# micr0x.net
KiCad netlist of a schematic drawn in EAGLE
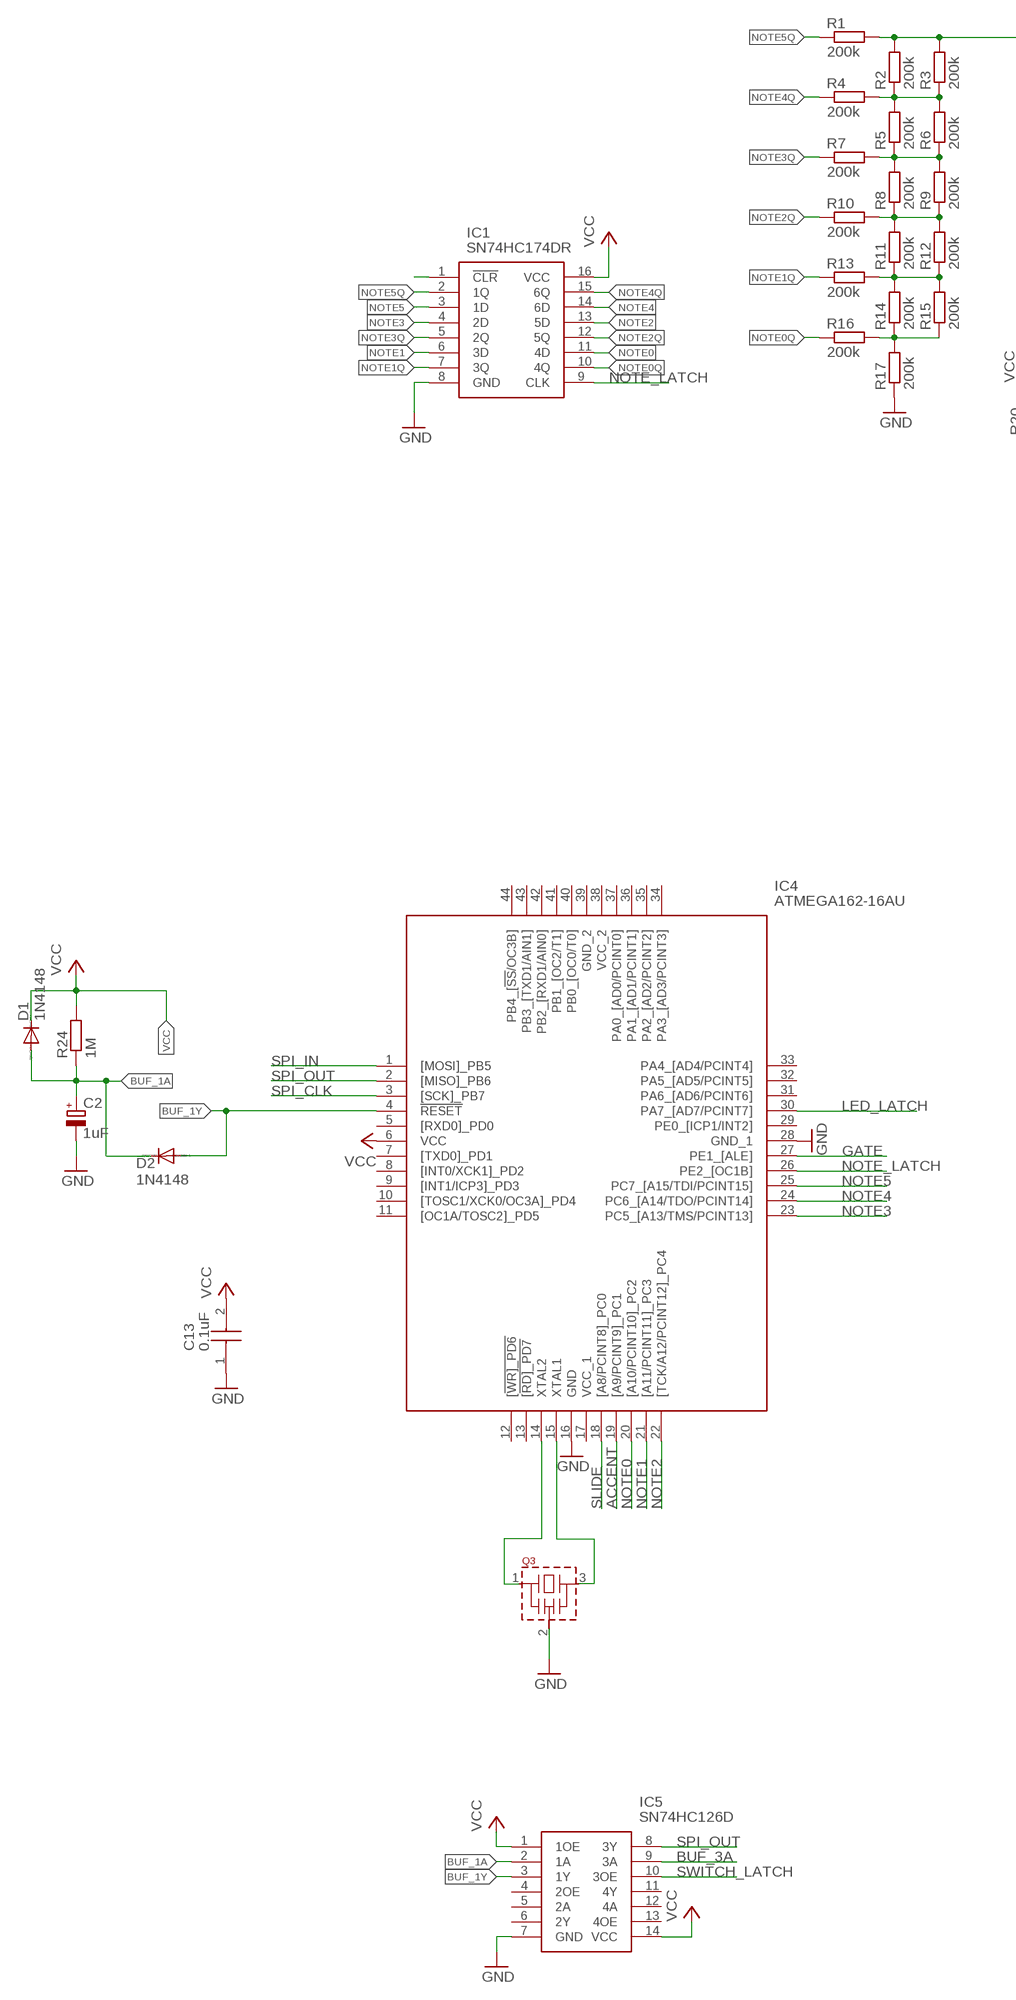
[diagram p0: schematic, sheet 1, part 1 of 2]
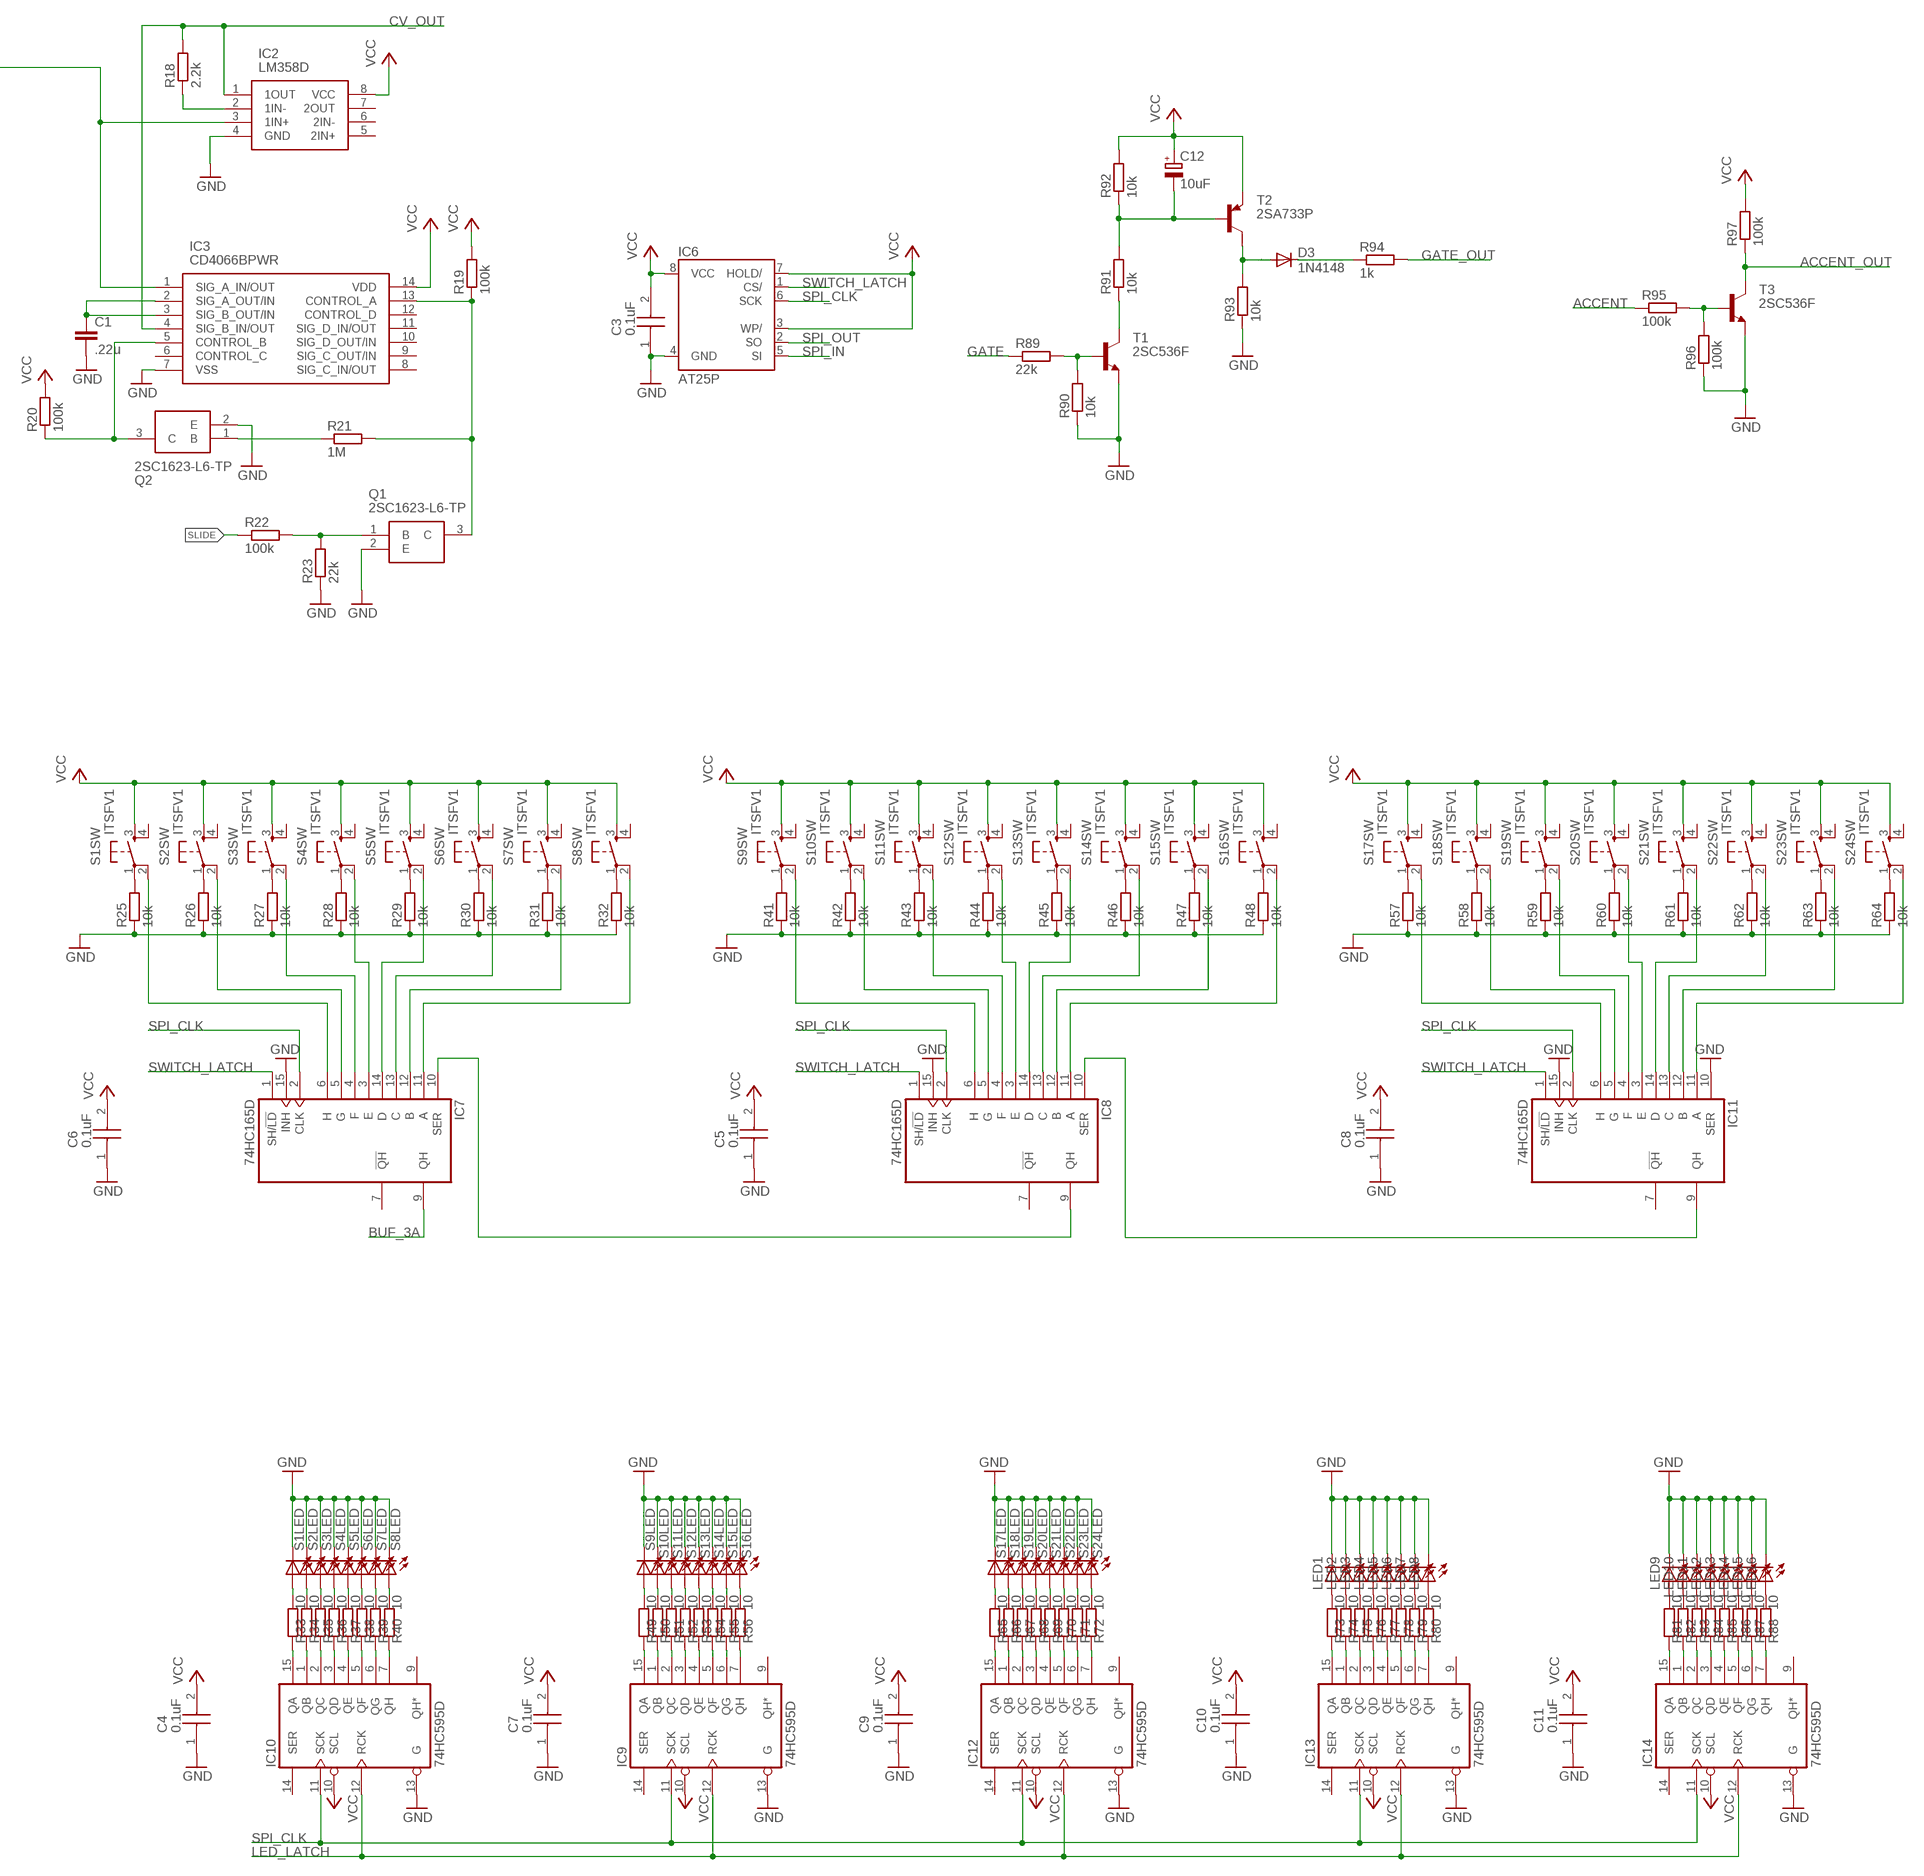
[diagram p1: schematic, sheet 1, part 2 of 2]

(export (version "E")
  (design (tool "Eeschema 10.0.6"))
  (components
    (comp (ref "C1")
      (value ".22u")
      (footprint "eagle-import:C075-032X103")
      (fields (field (name "MOUSER_PART_NUMBER") "QYX2A224KTP"))
      (libsource (lib "eagle-import") (part "C-EU075-032X103"))
    )
    (comp (ref "C2")
      (value "1uF")
      (footprint "eagle-import:E2-5")
      (fields (field (name "MOUSER_PART_NUMBER") "140-REA1R0M2CBK0511P"))
      (libsource (lib "eagle-import") (part "CPOL-EUE2-5"))
    )
    (comp (ref "C3")
      (value "0.1uF")
      (footprint "eagle-import:CAPC1608X90N")
      (fields
        (field (name "MANUFACTURER_PART_NUMBER") "GCJ188R71H104KA12D")
        (field (name "MOUSER_PART_NUMBER") "81-GCJ188R71H104KA2D")
      )
      (libsource (lib "eagle-import") (part "GCJ188R71H104KA12D"))
    )
    (comp (ref "C4")
      (value "0.1uF")
      (footprint "eagle-import:CAPC1608X90N")
      (fields
        (field (name "MANUFACTURER_PART_NUMBER") "GCJ188R71H104KA12D")
        (field (name "MOUSER_PART_NUMBER") "81-GCJ188R71H104KA2D")
      )
      (libsource (lib "eagle-import") (part "GCJ188R71H104KA12D"))
    )
    (comp (ref "C5")
      (value "0.1uF")
      (footprint "eagle-import:CAPC1608X90N")
      (fields
        (field (name "MANUFACTURER_PART_NUMBER") "GCJ188R71H104KA12D")
        (field (name "MOUSER_PART_NUMBER") "81-GCJ188R71H104KA2D")
      )
      (libsource (lib "eagle-import") (part "GCJ188R71H104KA12D"))
    )
    (comp (ref "C6")
      (value "0.1uF")
      (footprint "eagle-import:CAPC1608X90N")
      (fields
        (field (name "MANUFACTURER_PART_NUMBER") "GCJ188R71H104KA12D")
        (field (name "MOUSER_PART_NUMBER") "81-GCJ188R71H104KA2D")
      )
      (libsource (lib "eagle-import") (part "GCJ188R71H104KA12D"))
    )
    (comp (ref "C7")
      (value "0.1uF")
      (footprint "eagle-import:CAPC1608X90N")
      (fields
        (field (name "MANUFACTURER_PART_NUMBER") "GCJ188R71H104KA12D")
        (field (name "MOUSER_PART_NUMBER") "81-GCJ188R71H104KA2D")
      )
      (libsource (lib "eagle-import") (part "GCJ188R71H104KA12D"))
    )
    (comp (ref "C8")
      (value "0.1uF")
      (footprint "eagle-import:CAPC1608X90N")
      (fields
        (field (name "MANUFACTURER_PART_NUMBER") "GCJ188R71H104KA12D")
        (field (name "MOUSER_PART_NUMBER") "81-GCJ188R71H104KA2D")
      )
      (libsource (lib "eagle-import") (part "GCJ188R71H104KA12D"))
    )
    (comp (ref "C9")
      (value "0.1uF")
      (footprint "eagle-import:CAPC1608X90N")
      (fields
        (field (name "MANUFACTURER_PART_NUMBER") "GCJ188R71H104KA12D")
        (field (name "MOUSER_PART_NUMBER") "81-GCJ188R71H104KA2D")
      )
      (libsource (lib "eagle-import") (part "GCJ188R71H104KA12D"))
    )
    (comp (ref "C10")
      (value "0.1uF")
      (footprint "eagle-import:CAPC1608X90N")
      (fields
        (field (name "MANUFACTURER_PART_NUMBER") "GCJ188R71H104KA12D")
        (field (name "MOUSER_PART_NUMBER") "81-GCJ188R71H104KA2D")
      )
      (libsource (lib "eagle-import") (part "GCJ188R71H104KA12D"))
    )
    (comp (ref "C11")
      (value "0.1uF")
      (footprint "eagle-import:CAPC1608X90N")
      (fields
        (field (name "MANUFACTURER_PART_NUMBER") "GCJ188R71H104KA12D")
        (field (name "MOUSER_PART_NUMBER") "81-GCJ188R71H104KA2D")
      )
      (libsource (lib "eagle-import") (part "GCJ188R71H104KA12D"))
    )
    (comp (ref "C12")
      (value "10uF")
      (footprint "eagle-import:E2-5")
      (libsource (lib "eagle-import") (part "CPOL-EUE2-5"))
    )
    (comp (ref "C13")
      (value "0.1uF")
      (footprint "eagle-import:CAPC1608X90N")
      (fields
        (field (name "MANUFACTURER_PART_NUMBER") "GCJ188R71H104KA12D")
        (field (name "MOUSER_PART_NUMBER") "81-GCJ188R71H104KA2D")
      )
      (libsource (lib "eagle-import") (part "GCJ188R71H104KA12D"))
    )
    (comp (ref "D1")
      (value "1N4148")
      (footprint "eagle-import:DO35-7")
      (libsource (lib "eagle-import") (part "1N4148DO35-7"))
    )
    (comp (ref "D2")
      (value "1N4148")
      (footprint "eagle-import:DO35-7")
      (libsource (lib "eagle-import") (part "1N4148DO35-7"))
    )
    (comp (ref "D3")
      (value "1N4148")
      (footprint "eagle-import:DO35-7")
      (libsource (lib "eagle-import") (part "1N4148DO35-7"))
    )
    (comp (ref "IC1")
      (value "SN74HC174DR")
      (footprint "eagle-import:SOIC127P600X175-16N")
      (fields (field (name "MOUSER_PART_NUMBER") "595-SN74HC174DR"))
      (libsource (lib "eagle-import") (part "SN74HC174DR"))
    )
    (comp (ref "IC2")
      (value "LM358D")
      (footprint "eagle-import:SOIC127P600X175-8N")
      (fields (field (name "MOUSER_PART_NUMBER") "595-LM358D"))
      (libsource (lib "eagle-import") (part "LM358D"))
    )
    (comp (ref "IC3")
      (value "CD4066BPWR")
      (footprint "eagle-import:SOP65P640X120-14N")
      (libsource (lib "eagle-import") (part "CD4066BPWR"))
    )
    (comp (ref "IC4")
      (value "ATMEGA162-16AU")
      (footprint "eagle-import:QFP80P1200X1200X120-44N")
      (fields (field (name "MOUSER_PART_NUMBER") "556-ATMEGA162-16AU"))
      (libsource (lib "eagle-import") (part "ATMEGA162-16AU"))
    )
    (comp (ref "IC5")
      (value "SN74HC126D")
      (footprint "eagle-import:SOIC127P600X175-14N")
      (fields (field (name "MOUSER_PART_NUMBER") "595-SN74HC126D"))
      (libsource (lib "eagle-import") (part "SN74HC126D"))
    )
    (comp (ref "IC6")
      (value "AT25P")
      (footprint "eagle-import:DIL08")
      (fields (field (name "MPN") "CAT25040LI-G"))
      (libsource (lib "eagle-import") (part "AT25P"))
    )
    (comp (ref "IC7")
      (value "74HC165D")
      (footprint "eagle-import:SO16")
      (libsource (lib "eagle-import") (part "74165DHC"))
    )
    (comp (ref "IC8")
      (value "74HC165D")
      (footprint "eagle-import:SO16")
      (libsource (lib "eagle-import") (part "74165DHC"))
    )
    (comp (ref "IC9")
      (value "74HC595D")
      (footprint "eagle-import:SO16")
      (libsource (lib "eagle-import") (part "74595DHC"))
    )
    (comp (ref "IC10")
      (value "74HC595D")
      (footprint "eagle-import:SO16")
      (libsource (lib "eagle-import") (part "74595DHC"))
    )
    (comp (ref "IC11")
      (value "74HC165D")
      (footprint "eagle-import:SO16")
      (libsource (lib "eagle-import") (part "74165DHC"))
    )
    (comp (ref "IC12")
      (value "74HC595D")
      (footprint "eagle-import:SO16")
      (libsource (lib "eagle-import") (part "74595DHC"))
    )
    (comp (ref "IC13")
      (value "74HC595D")
      (footprint "eagle-import:SO16")
      (libsource (lib "eagle-import") (part "74595DHC"))
    )
    (comp (ref "IC14")
      (value "74HC595D")
      (footprint "eagle-import:SO16")
      (libsource (lib "eagle-import") (part "74595DHC"))
    )
    (comp (ref "LED1")
      (value "LED3MM")
      (footprint "eagle-import:LED3MM")
      (libsource (lib "eagle-import") (part "LED3MM"))
    )
    (comp (ref "LED2")
      (value "LED3MM")
      (footprint "eagle-import:LED3MM")
      (libsource (lib "eagle-import") (part "LED3MM"))
    )
    (comp (ref "LED3")
      (value "LED3MM")
      (footprint "eagle-import:LED3MM")
      (libsource (lib "eagle-import") (part "LED3MM"))
    )
    (comp (ref "LED4")
      (value "LED3MM")
      (footprint "eagle-import:LED3MM")
      (libsource (lib "eagle-import") (part "LED3MM"))
    )
    (comp (ref "LED5")
      (value "LED3MM")
      (footprint "eagle-import:LED3MM")
      (libsource (lib "eagle-import") (part "LED3MM"))
    )
    (comp (ref "LED6")
      (value "LED3MM")
      (footprint "eagle-import:LED3MM")
      (libsource (lib "eagle-import") (part "LED3MM"))
    )
    (comp (ref "LED7")
      (value "LED3MM")
      (footprint "eagle-import:LED3MM")
      (libsource (lib "eagle-import") (part "LED3MM"))
    )
    (comp (ref "LED8")
      (value "LED3MM")
      (footprint "eagle-import:LED3MM")
      (libsource (lib "eagle-import") (part "LED3MM"))
    )
    (comp (ref "LED9")
      (value "LED3MM")
      (footprint "eagle-import:LED3MM")
      (libsource (lib "eagle-import") (part "LED3MM"))
    )
    (comp (ref "LED10")
      (value "LED3MM")
      (footprint "eagle-import:LED3MM")
      (libsource (lib "eagle-import") (part "LED3MM"))
    )
    (comp (ref "LED11")
      (value "LED3MM")
      (footprint "eagle-import:LED3MM")
      (libsource (lib "eagle-import") (part "LED3MM"))
    )
    (comp (ref "LED12")
      (value "LED3MM")
      (footprint "eagle-import:LED3MM")
      (libsource (lib "eagle-import") (part "LED3MM"))
    )
    (comp (ref "LED13")
      (value "LED3MM")
      (footprint "eagle-import:LED3MM")
      (libsource (lib "eagle-import") (part "LED3MM"))
    )
    (comp (ref "LED14")
      (value "LED3MM")
      (footprint "eagle-import:LED3MM")
      (libsource (lib "eagle-import") (part "LED3MM"))
    )
    (comp (ref "LED15")
      (value "LED3MM")
      (footprint "eagle-import:LED3MM")
      (libsource (lib "eagle-import") (part "LED3MM"))
    )
    (comp (ref "LED16")
      (value "LED3MM")
      (footprint "eagle-import:LED3MM")
      (libsource (lib "eagle-import") (part "LED3MM"))
    )
    (comp (ref "Q1")
      (value "2SC1623-L6-TP")
      (footprint "eagle-import:SOT96P237X112-3N")
      (libsource (lib "eagle-import") (part "2SC1623-L6-TP"))
    )
    (comp (ref "Q2")
      (value "2SC1623-L6-TP")
      (footprint "eagle-import:SOT96P237X112-3N")
      (libsource (lib "eagle-import") (part "2SC1623-L6-TP"))
    )
    (comp (ref "Q3")
      (value "CSTLS_X")
      (footprint "eagle-import:CSTLS_X")
      (libsource (lib "eagle-import") (part "CSTLS_X"))
    )
    (comp (ref "R1")
      (value "200k")
      (footprint "eagle-import:R0603")
      (fields (field (name "MOUSER_PART_NUMBER") " RCS0603200KFKEA"))
      (libsource (lib "eagle-import") (part "R-EU_R0603"))
    )
    (comp (ref "R2")
      (value "200k")
      (footprint "eagle-import:R0603")
      (fields (field (name "MOUSER_PART_NUMBER") " RCS0603200KFKEA"))
      (libsource (lib "eagle-import") (part "R-EU_R0603"))
    )
    (comp (ref "R3")
      (value "200k")
      (footprint "eagle-import:R0603")
      (fields (field (name "MOUSER_PART_NUMBER") "RCS0603200KFKEA"))
      (libsource (lib "eagle-import") (part "R-EU_R0603"))
    )
    (comp (ref "R4")
      (value "200k")
      (footprint "eagle-import:R0603")
      (fields (field (name "MOUSER_PART_NUMBER") " RCS0603200KFKEA"))
      (libsource (lib "eagle-import") (part "R-EU_R0603"))
    )
    (comp (ref "R5")
      (value "200k")
      (footprint "eagle-import:R0603")
      (fields (field (name "MOUSER_PART_NUMBER") " RCS0603200KFKEA"))
      (libsource (lib "eagle-import") (part "R-EU_R0603"))
    )
    (comp (ref "R6")
      (value "200k")
      (footprint "eagle-import:R0603")
      (fields (field (name "MOUSER_PART_NUMBER") " RCS0603200KFKEA"))
      (libsource (lib "eagle-import") (part "R-EU_R0603"))
    )
    (comp (ref "R7")
      (value "200k")
      (footprint "eagle-import:R0603")
      (fields (field (name "MOUSER_PART_NUMBER") " RCS0603200KFKEA"))
      (libsource (lib "eagle-import") (part "R-EU_R0603"))
    )
    (comp (ref "R8")
      (value "200k")
      (footprint "eagle-import:R0603")
      (fields (field (name "MOUSER_PART_NUMBER") " RCS0603200KFKEA"))
      (libsource (lib "eagle-import") (part "R-EU_R0603"))
    )
    (comp (ref "R9")
      (value "200k")
      (footprint "eagle-import:R0603")
      (fields (field (name "MOUSER_PART_NUMBER") " RCS0603200KFKEA"))
      (libsource (lib "eagle-import") (part "R-EU_R0603"))
    )
    (comp (ref "R10")
      (value "200k")
      (footprint "eagle-import:R0603")
      (fields (field (name "MOUSER_PART_NUMBER") " RCS0603200KFKEA"))
      (libsource (lib "eagle-import") (part "R-EU_R0603"))
    )
    (comp (ref "R11")
      (value "200k")
      (footprint "eagle-import:R0603")
      (fields (field (name "MOUSER_PART_NUMBER") " RCS0603200KFKEA"))
      (libsource (lib "eagle-import") (part "R-EU_R0603"))
    )
    (comp (ref "R12")
      (value "200k")
      (footprint "eagle-import:R0603")
      (fields (field (name "MOUSER_PART_NUMBER") " RCS0603200KFKEA"))
      (libsource (lib "eagle-import") (part "R-EU_R0603"))
    )
    (comp (ref "R13")
      (value "200k")
      (footprint "eagle-import:R0603")
      (fields (field (name "MOUSER_PART_NUMBER") " RCS0603200KFKEA"))
      (libsource (lib "eagle-import") (part "R-EU_R0603"))
    )
    (comp (ref "R14")
      (value "200k")
      (footprint "eagle-import:R0603")
      (fields (field (name "MOUSER_PART_NUMBER") " RCS0603200KFKEA"))
      (libsource (lib "eagle-import") (part "R-EU_R0603"))
    )
    (comp (ref "R15")
      (value "200k")
      (footprint "eagle-import:R0603")
      (fields (field (name "MOUSER_PART_NUMBER") " RCS0603200KFKEA"))
      (libsource (lib "eagle-import") (part "R-EU_R0603"))
    )
    (comp (ref "R16")
      (value "200k")
      (footprint "eagle-import:R0603")
      (fields (field (name "MOUSER_PART_NUMBER") " RCS0603200KFKEA"))
      (libsource (lib "eagle-import") (part "R-EU_R0603"))
    )
    (comp (ref "R17")
      (value "200k")
      (footprint "eagle-import:R0603")
      (fields (field (name "MOUSER_PART_NUMBER") " RCS0603200KFKEA"))
      (libsource (lib "eagle-import") (part "R-EU_R0603"))
    )
    (comp (ref "R18")
      (value "2.2k")
      (footprint "eagle-import:R0603")
      (fields (field (name "MOUSER_PART_NUMBER") "RCS06032K20JNEA"))
      (libsource (lib "eagle-import") (part "R-EU_R0603"))
    )
    (comp (ref "R19")
      (value "100k")
      (footprint "eagle-import:R0603")
      (fields (field (name "MOUSER_PART_NUMBER") "RCS0603100KJNEA"))
      (libsource (lib "eagle-import") (part "R-EU_R0603"))
    )
    (comp (ref "R20")
      (value "100k")
      (footprint "eagle-import:R0603")
      (fields (field (name "MOUSER_PART_NUMBER") "RCS0603100KJNEA"))
      (libsource (lib "eagle-import") (part "R-EU_R0603"))
    )
    (comp (ref "R21")
      (value "1M")
      (footprint "eagle-import:R0603")
      (fields (field (name "MOUSER_PART_NUMBER") "RCS06031M00JNEA"))
      (libsource (lib "eagle-import") (part "R-EU_R0603"))
    )
    (comp (ref "R22")
      (value "100k")
      (footprint "eagle-import:R0603")
      (fields (field (name "MOUSER_PART_NUMBER") "RCS0603100KJNEA"))
      (libsource (lib "eagle-import") (part "R-EU_R0603"))
    )
    (comp (ref "R23")
      (value "22k")
      (footprint "eagle-import:R0603")
      (fields (field (name "MOUSER_PART_NUMBER") "RCS060322K0JNEA"))
      (libsource (lib "eagle-import") (part "R-EU_R0603"))
    )
    (comp (ref "R24")
      (value "1M")
      (footprint "eagle-import:R0603")
      (fields (field (name "MOUSER_PART_NUMBER") "RCS06031M00JNEA"))
      (libsource (lib "eagle-import") (part "R-EU_R0603"))
    )
    (comp (ref "R25")
      (value "10k")
      (footprint "eagle-import:R0603")
      (fields (field (name "MOUSER_PART_NUMBER") "RCS060310K0JNEA"))
      (libsource (lib "eagle-import") (part "R-EU_R0603"))
    )
    (comp (ref "R26")
      (value "10k")
      (footprint "eagle-import:R0603")
      (fields (field (name "MOUSER_PART_NUMBER") "RCS060310K0JNEA"))
      (libsource (lib "eagle-import") (part "R-EU_R0603"))
    )
    (comp (ref "R27")
      (value "10k")
      (footprint "eagle-import:R0603")
      (fields (field (name "MOUSER_PART_NUMBER") "RCS060310K0JNEA"))
      (libsource (lib "eagle-import") (part "R-EU_R0603"))
    )
    (comp (ref "R28")
      (value "10k")
      (footprint "eagle-import:R0603")
      (fields (field (name "MOUSER_PART_NUMBER") "RCS060310K0JNEA"))
      (libsource (lib "eagle-import") (part "R-EU_R0603"))
    )
    (comp (ref "R29")
      (value "10k")
      (footprint "eagle-import:R0603")
      (fields (field (name "MOUSER_PART_NUMBER") "RCS060310K0JNEA"))
      (libsource (lib "eagle-import") (part "R-EU_R0603"))
    )
    (comp (ref "R30")
      (value "10k")
      (footprint "eagle-import:R0603")
      (fields (field (name "MOUSER_PART_NUMBER") "RCS060310K0JNEA"))
      (libsource (lib "eagle-import") (part "R-EU_R0603"))
    )
    (comp (ref "R31")
      (value "10k")
      (footprint "eagle-import:R0603")
      (fields (field (name "MOUSER_PART_NUMBER") "RCS060310K0JNEA"))
      (libsource (lib "eagle-import") (part "R-EU_R0603"))
    )
    (comp (ref "R32")
      (value "10k")
      (footprint "eagle-import:R0603")
      (fields (field (name "MOUSER_PART_NUMBER") "RCS060310K0JNEA"))
      (libsource (lib "eagle-import") (part "R-EU_R0603"))
    )
    (comp (ref "R33")
      (value "10")
      (footprint "eagle-import:R0603")
      (fields (field (name "MOUSER_PART_NUMBER") " RCS0603200KFKEA"))
      (libsource (lib "eagle-import") (part "R-EU_R0603"))
    )
    (comp (ref "R34")
      (value "10")
      (footprint "eagle-import:R0603")
      (fields (field (name "MOUSER_PART_NUMBER") " RCS0603200KFKEA"))
      (libsource (lib "eagle-import") (part "R-EU_R0603"))
    )
    (comp (ref "R35")
      (value "10")
      (footprint "eagle-import:R0603")
      (fields (field (name "MOUSER_PART_NUMBER") " RCS0603200KFKEA"))
      (libsource (lib "eagle-import") (part "R-EU_R0603"))
    )
    (comp (ref "R36")
      (value "10")
      (footprint "eagle-import:R0603")
      (fields (field (name "MOUSER_PART_NUMBER") " RCS0603200KFKEA"))
      (libsource (lib "eagle-import") (part "R-EU_R0603"))
    )
    (comp (ref "R37")
      (value "10")
      (footprint "eagle-import:R0603")
      (fields (field (name "MOUSER_PART_NUMBER") " RCS0603200KFKEA"))
      (libsource (lib "eagle-import") (part "R-EU_R0603"))
    )
    (comp (ref "R38")
      (value "10")
      (footprint "eagle-import:R0603")
      (fields (field (name "MOUSER_PART_NUMBER") " RCS0603200KFKEA"))
      (libsource (lib "eagle-import") (part "R-EU_R0603"))
    )
    (comp (ref "R39")
      (value "10")
      (footprint "eagle-import:R0603")
      (fields (field (name "MOUSER_PART_NUMBER") " RCS0603200KFKEA"))
      (libsource (lib "eagle-import") (part "R-EU_R0603"))
    )
    (comp (ref "R40")
      (value "10")
      (footprint "eagle-import:R0603")
      (fields (field (name "MOUSER_PART_NUMBER") " RCS0603200KFKEA"))
      (libsource (lib "eagle-import") (part "R-EU_R0603"))
    )
    (comp (ref "R41")
      (value "10k")
      (footprint "eagle-import:R0603")
      (fields (field (name "MOUSER_PART_NUMBER") "RCS060310K0JNEA"))
      (libsource (lib "eagle-import") (part "R-EU_R0603"))
    )
    (comp (ref "R42")
      (value "10k")
      (footprint "eagle-import:R0603")
      (fields (field (name "MOUSER_PART_NUMBER") "RCS060310K0JNEA"))
      (libsource (lib "eagle-import") (part "R-EU_R0603"))
    )
    (comp (ref "R43")
      (value "10k")
      (footprint "eagle-import:R0603")
      (fields (field (name "MOUSER_PART_NUMBER") "RCS060310K0JNEA"))
      (libsource (lib "eagle-import") (part "R-EU_R0603"))
    )
    (comp (ref "R44")
      (value "10k")
      (footprint "eagle-import:R0603")
      (fields (field (name "MOUSER_PART_NUMBER") "RCS060310K0JNEA"))
      (libsource (lib "eagle-import") (part "R-EU_R0603"))
    )
    (comp (ref "R45")
      (value "10k")
      (footprint "eagle-import:R0603")
      (fields (field (name "MOUSER_PART_NUMBER") "RCS060310K0JNEA"))
      (libsource (lib "eagle-import") (part "R-EU_R0603"))
    )
    (comp (ref "R46")
      (value "10k")
      (footprint "eagle-import:R0603")
      (fields (field (name "MOUSER_PART_NUMBER") "RCS060310K0JNEA"))
      (libsource (lib "eagle-import") (part "R-EU_R0603"))
    )
    (comp (ref "R47")
      (value "10k")
      (footprint "eagle-import:R0603")
      (fields (field (name "MOUSER_PART_NUMBER") "RCS060310K0JNEA"))
      (libsource (lib "eagle-import") (part "R-EU_R0603"))
    )
    (comp (ref "R48")
      (value "10k")
      (footprint "eagle-import:R0603")
      (fields (field (name "MOUSER_PART_NUMBER") "RCS060310K0JNEA"))
      (libsource (lib "eagle-import") (part "R-EU_R0603"))
    )
    (comp (ref "R49")
      (value "10")
      (footprint "eagle-import:R0603")
      (fields (field (name "MOUSER_PART_NUMBER") " RCS0603200KFKEA"))
      (libsource (lib "eagle-import") (part "R-EU_R0603"))
    )
    (comp (ref "R50")
      (value "10")
      (footprint "eagle-import:R0603")
      (fields (field (name "MOUSER_PART_NUMBER") " RCS0603200KFKEA"))
      (libsource (lib "eagle-import") (part "R-EU_R0603"))
    )
    (comp (ref "R51")
      (value "10")
      (footprint "eagle-import:R0603")
      (fields (field (name "MOUSER_PART_NUMBER") " RCS0603200KFKEA"))
      (libsource (lib "eagle-import") (part "R-EU_R0603"))
    )
    (comp (ref "R52")
      (value "10")
      (footprint "eagle-import:R0603")
      (fields (field (name "MOUSER_PART_NUMBER") " RCS0603200KFKEA"))
      (libsource (lib "eagle-import") (part "R-EU_R0603"))
    )
    (comp (ref "R53")
      (value "10")
      (footprint "eagle-import:R0603")
      (fields (field (name "MOUSER_PART_NUMBER") " RCS0603200KFKEA"))
      (libsource (lib "eagle-import") (part "R-EU_R0603"))
    )
    (comp (ref "R54")
      (value "10")
      (footprint "eagle-import:R0603")
      (fields (field (name "MOUSER_PART_NUMBER") " RCS0603200KFKEA"))
      (libsource (lib "eagle-import") (part "R-EU_R0603"))
    )
    (comp (ref "R55")
      (value "10")
      (footprint "eagle-import:R0603")
      (fields (field (name "MOUSER_PART_NUMBER") " RCS0603200KFKEA"))
      (libsource (lib "eagle-import") (part "R-EU_R0603"))
    )
    (comp (ref "R56")
      (value "10")
      (footprint "eagle-import:R0603")
      (fields (field (name "MOUSER_PART_NUMBER") " RCS0603200KFKEA"))
      (libsource (lib "eagle-import") (part "R-EU_R0603"))
    )
    (comp (ref "R57")
      (value "10k")
      (footprint "eagle-import:R0603")
      (fields (field (name "MOUSER_PART_NUMBER") "RCS060310K0JNEA"))
      (libsource (lib "eagle-import") (part "R-EU_R0603"))
    )
    (comp (ref "R58")
      (value "10k")
      (footprint "eagle-import:R0603")
      (fields (field (name "MOUSER_PART_NUMBER") "RCS060310K0JNEA"))
      (libsource (lib "eagle-import") (part "R-EU_R0603"))
    )
    (comp (ref "R59")
      (value "10k")
      (footprint "eagle-import:R0603")
      (fields (field (name "MOUSER_PART_NUMBER") "RCS060310K0JNEA"))
      (libsource (lib "eagle-import") (part "R-EU_R0603"))
    )
    (comp (ref "R60")
      (value "10k")
      (footprint "eagle-import:R0603")
      (fields (field (name "MOUSER_PART_NUMBER") "RCS060310K0JNEA"))
      (libsource (lib "eagle-import") (part "R-EU_R0603"))
    )
    (comp (ref "R61")
      (value "10k")
      (footprint "eagle-import:R0603")
      (fields (field (name "MOUSER_PART_NUMBER") "RCS060310K0JNEA"))
      (libsource (lib "eagle-import") (part "R-EU_R0603"))
    )
    (comp (ref "R62")
      (value "10k")
      (footprint "eagle-import:R0603")
      (fields (field (name "MOUSER_PART_NUMBER") "RCS060310K0JNEA"))
      (libsource (lib "eagle-import") (part "R-EU_R0603"))
    )
    (comp (ref "R63")
      (value "10k")
      (footprint "eagle-import:R0603")
      (fields (field (name "MOUSER_PART_NUMBER") "RCS060310K0JNEA"))
      (libsource (lib "eagle-import") (part "R-EU_R0603"))
    )
    (comp (ref "R64")
      (value "10k")
      (footprint "eagle-import:R0603")
      (fields (field (name "MOUSER_PART_NUMBER") "RCS060310K0JNEA"))
      (libsource (lib "eagle-import") (part "R-EU_R0603"))
    )
    (comp (ref "R65")
      (value "10")
      (footprint "eagle-import:R0603")
      (fields (field (name "MOUSER_PART_NUMBER") " RCS0603200KFKEA"))
      (libsource (lib "eagle-import") (part "R-EU_R0603"))
    )
    (comp (ref "R66")
      (value "10")
      (footprint "eagle-import:R0603")
      (fields (field (name "MOUSER_PART_NUMBER") " RCS0603200KFKEA"))
      (libsource (lib "eagle-import") (part "R-EU_R0603"))
    )
    (comp (ref "R67")
      (value "10")
      (footprint "eagle-import:R0603")
      (fields (field (name "MOUSER_PART_NUMBER") " RCS0603200KFKEA"))
      (libsource (lib "eagle-import") (part "R-EU_R0603"))
    )
    (comp (ref "R68")
      (value "10")
      (footprint "eagle-import:R0603")
      (fields (field (name "MOUSER_PART_NUMBER") " RCS0603200KFKEA"))
      (libsource (lib "eagle-import") (part "R-EU_R0603"))
    )
    (comp (ref "R69")
      (value "10")
      (footprint "eagle-import:R0603")
      (fields (field (name "MOUSER_PART_NUMBER") " RCS0603200KFKEA"))
      (libsource (lib "eagle-import") (part "R-EU_R0603"))
    )
    (comp (ref "R70")
      (value "10")
      (footprint "eagle-import:R0603")
      (fields (field (name "MOUSER_PART_NUMBER") " RCS0603200KFKEA"))
      (libsource (lib "eagle-import") (part "R-EU_R0603"))
    )
    (comp (ref "R71")
      (value "10")
      (footprint "eagle-import:R0603")
      (fields (field (name "MOUSER_PART_NUMBER") " RCS0603200KFKEA"))
      (libsource (lib "eagle-import") (part "R-EU_R0603"))
    )
    (comp (ref "R72")
      (value "10")
      (footprint "eagle-import:R0603")
      (fields (field (name "MOUSER_PART_NUMBER") " RCS0603200KFKEA"))
      (libsource (lib "eagle-import") (part "R-EU_R0603"))
    )
    (comp (ref "R73")
      (value "10")
      (footprint "eagle-import:R0603")
      (fields (field (name "MOUSER_PART_NUMBER") " RCS0603200KFKEA"))
      (libsource (lib "eagle-import") (part "R-EU_R0603"))
    )
    (comp (ref "R74")
      (value "10")
      (footprint "eagle-import:R0603")
      (fields (field (name "MOUSER_PART_NUMBER") " RCS0603200KFKEA"))
      (libsource (lib "eagle-import") (part "R-EU_R0603"))
    )
    (comp (ref "R75")
      (value "10")
      (footprint "eagle-import:R0603")
      (fields (field (name "MOUSER_PART_NUMBER") " RCS0603200KFKEA"))
      (libsource (lib "eagle-import") (part "R-EU_R0603"))
    )
    (comp (ref "R76")
      (value "10")
      (footprint "eagle-import:R0603")
      (fields (field (name "MOUSER_PART_NUMBER") " RCS0603200KFKEA"))
      (libsource (lib "eagle-import") (part "R-EU_R0603"))
    )
    (comp (ref "R77")
      (value "10")
      (footprint "eagle-import:R0603")
      (fields (field (name "MOUSER_PART_NUMBER") " RCS0603200KFKEA"))
      (libsource (lib "eagle-import") (part "R-EU_R0603"))
    )
    (comp (ref "R78")
      (value "10")
      (footprint "eagle-import:R0603")
      (fields (field (name "MOUSER_PART_NUMBER") " RCS0603200KFKEA"))
      (libsource (lib "eagle-import") (part "R-EU_R0603"))
    )
    (comp (ref "R79")
      (value "10")
      (footprint "eagle-import:R0603")
      (fields (field (name "MOUSER_PART_NUMBER") " RCS0603200KFKEA"))
      (libsource (lib "eagle-import") (part "R-EU_R0603"))
    )
    (comp (ref "R80")
      (value "10")
      (footprint "eagle-import:R0603")
      (fields (field (name "MOUSER_PART_NUMBER") " RCS0603200KFKEA"))
      (libsource (lib "eagle-import") (part "R-EU_R0603"))
    )
    (comp (ref "R81")
      (value "10")
      (footprint "eagle-import:R0603")
      (fields (field (name "MOUSER_PART_NUMBER") " RCS0603200KFKEA"))
      (libsource (lib "eagle-import") (part "R-EU_R0603"))
    )
    (comp (ref "R82")
      (value "10")
      (footprint "eagle-import:R0603")
      (fields (field (name "MOUSER_PART_NUMBER") " RCS0603200KFKEA"))
      (libsource (lib "eagle-import") (part "R-EU_R0603"))
    )
    (comp (ref "R83")
      (value "10")
      (footprint "eagle-import:R0603")
      (fields (field (name "MOUSER_PART_NUMBER") " RCS0603200KFKEA"))
      (libsource (lib "eagle-import") (part "R-EU_R0603"))
    )
    (comp (ref "R84")
      (value "10")
      (footprint "eagle-import:R0603")
      (fields (field (name "MOUSER_PART_NUMBER") " RCS0603200KFKEA"))
      (libsource (lib "eagle-import") (part "R-EU_R0603"))
    )
    (comp (ref "R85")
      (value "10")
      (footprint "eagle-import:R0603")
      (fields (field (name "MOUSER_PART_NUMBER") " RCS0603200KFKEA"))
      (libsource (lib "eagle-import") (part "R-EU_R0603"))
    )
    (comp (ref "R86")
      (value "10")
      (footprint "eagle-import:R0603")
      (fields (field (name "MOUSER_PART_NUMBER") " RCS0603200KFKEA"))
      (libsource (lib "eagle-import") (part "R-EU_R0603"))
    )
    (comp (ref "R87")
      (value "10")
      (footprint "eagle-import:R0603")
      (fields (field (name "MOUSER_PART_NUMBER") " RCS0603200KFKEA"))
      (libsource (lib "eagle-import") (part "R-EU_R0603"))
    )
    (comp (ref "R88")
      (value "10")
      (footprint "eagle-import:R0603")
      (fields (field (name "MOUSER_PART_NUMBER") " RCS0603200KFKEA"))
      (libsource (lib "eagle-import") (part "R-EU_R0603"))
    )
    (comp (ref "R89")
      (value "22k")
      (footprint "eagle-import:R0603")
      (fields (field (name "MOUSER_PART_NUMBER") "RCS060310K0JNEA"))
      (libsource (lib "eagle-import") (part "R-EU_R0603"))
    )
    (comp (ref "R90")
      (value "10k")
      (footprint "eagle-import:R0603")
      (fields (field (name "MOUSER_PART_NUMBER") "RCS060310K0JNEA"))
      (libsource (lib "eagle-import") (part "R-EU_R0603"))
    )
    (comp (ref "R91")
      (value "10k")
      (footprint "eagle-import:R0603")
      (fields (field (name "MOUSER_PART_NUMBER") "RCS060310K0JNEA"))
      (libsource (lib "eagle-import") (part "R-EU_R0603"))
    )
    (comp (ref "R92")
      (value "10k")
      (footprint "eagle-import:R0603")
      (fields (field (name "MOUSER_PART_NUMBER") "RCS060310K0JNEA"))
      (libsource (lib "eagle-import") (part "R-EU_R0603"))
    )
    (comp (ref "R93")
      (value "10k")
      (footprint "eagle-import:R0603")
      (fields (field (name "MOUSER_PART_NUMBER") "RCS060310K0JNEA"))
      (libsource (lib "eagle-import") (part "R-EU_R0603"))
    )
    (comp (ref "R94")
      (value "1k")
      (footprint "eagle-import:R0603")
      (fields (field (name "MOUSER_PART_NUMBER") "RCS060310K0JNEA"))
      (libsource (lib "eagle-import") (part "R-EU_R0603"))
    )
    (comp (ref "R95")
      (value "100k")
      (footprint "eagle-import:R0603")
      (fields (field (name "MOUSER_PART_NUMBER") "RCS060310K0JNEA"))
      (libsource (lib "eagle-import") (part "R-EU_R0603"))
    )
    (comp (ref "R96")
      (value "100k")
      (footprint "eagle-import:R0603")
      (fields (field (name "MOUSER_PART_NUMBER") "RCS060310K0JNEA"))
      (libsource (lib "eagle-import") (part "R-EU_R0603"))
    )
    (comp (ref "R97")
      (value "100k")
      (footprint "eagle-import:R0603")
      (fields (field (name "MOUSER_PART_NUMBER") "RCS060310K0JNEA"))
      (libsource (lib "eagle-import") (part "R-EU_R0603"))
    )
    (comp (ref "S1")
      (value "ITSFV1")
      (footprint "eagle-import:ITSFV1")
      (libsource (lib "eagle-import") (part "ITSFV1"))
    )
    (comp (ref "S2")
      (value "ITSFV1")
      (footprint "eagle-import:ITSFV1")
      (libsource (lib "eagle-import") (part "ITSFV1"))
    )
    (comp (ref "S3")
      (value "ITSFV1")
      (footprint "eagle-import:ITSFV1")
      (libsource (lib "eagle-import") (part "ITSFV1"))
    )
    (comp (ref "S4")
      (value "ITSFV1")
      (footprint "eagle-import:ITSFV1")
      (libsource (lib "eagle-import") (part "ITSFV1"))
    )
    (comp (ref "S5")
      (value "ITSFV1")
      (footprint "eagle-import:ITSFV1")
      (libsource (lib "eagle-import") (part "ITSFV1"))
    )
    (comp (ref "S6")
      (value "ITSFV1")
      (footprint "eagle-import:ITSFV1")
      (libsource (lib "eagle-import") (part "ITSFV1"))
    )
    (comp (ref "S7")
      (value "ITSFV1")
      (footprint "eagle-import:ITSFV1")
      (libsource (lib "eagle-import") (part "ITSFV1"))
    )
    (comp (ref "S8")
      (value "ITSFV1")
      (footprint "eagle-import:ITSFV1")
      (libsource (lib "eagle-import") (part "ITSFV1"))
    )
    (comp (ref "S9")
      (value "ITSFV1")
      (footprint "eagle-import:ITSFV1")
      (libsource (lib "eagle-import") (part "ITSFV1"))
    )
    (comp (ref "S10")
      (value "ITSFV1")
      (footprint "eagle-import:ITSFV1")
      (libsource (lib "eagle-import") (part "ITSFV1"))
    )
    (comp (ref "S11")
      (value "ITSFV1")
      (footprint "eagle-import:ITSFV1")
      (libsource (lib "eagle-import") (part "ITSFV1"))
    )
    (comp (ref "S12")
      (value "ITSFV1")
      (footprint "eagle-import:ITSFV1")
      (libsource (lib "eagle-import") (part "ITSFV1"))
    )
    (comp (ref "S13")
      (value "ITSFV1")
      (footprint "eagle-import:ITSFV1")
      (libsource (lib "eagle-import") (part "ITSFV1"))
    )
    (comp (ref "S14")
      (value "ITSFV1")
      (footprint "eagle-import:ITSFV1")
      (libsource (lib "eagle-import") (part "ITSFV1"))
    )
    (comp (ref "S15")
      (value "ITSFV1")
      (footprint "eagle-import:ITSFV1")
      (libsource (lib "eagle-import") (part "ITSFV1"))
    )
    (comp (ref "S16")
      (value "ITSFV1")
      (footprint "eagle-import:ITSFV1")
      (libsource (lib "eagle-import") (part "ITSFV1"))
    )
    (comp (ref "S17")
      (value "ITSFV1")
      (footprint "eagle-import:ITSFV1")
      (libsource (lib "eagle-import") (part "ITSFV1"))
    )
    (comp (ref "S18")
      (value "ITSFV1")
      (footprint "eagle-import:ITSFV1")
      (libsource (lib "eagle-import") (part "ITSFV1"))
    )
    (comp (ref "S19")
      (value "ITSFV1")
      (footprint "eagle-import:ITSFV1")
      (libsource (lib "eagle-import") (part "ITSFV1"))
    )
    (comp (ref "S20")
      (value "ITSFV1")
      (footprint "eagle-import:ITSFV1")
      (libsource (lib "eagle-import") (part "ITSFV1"))
    )
    (comp (ref "S21")
      (value "ITSFV1")
      (footprint "eagle-import:ITSFV1")
      (libsource (lib "eagle-import") (part "ITSFV1"))
    )
    (comp (ref "S22")
      (value "ITSFV1")
      (footprint "eagle-import:ITSFV1")
      (libsource (lib "eagle-import") (part "ITSFV1"))
    )
    (comp (ref "S23")
      (value "ITSFV1")
      (footprint "eagle-import:ITSFV1")
      (libsource (lib "eagle-import") (part "ITSFV1"))
    )
    (comp (ref "S24")
      (value "ITSFV1")
      (footprint "eagle-import:ITSFV1")
      (libsource (lib "eagle-import") (part "ITSFV1"))
    )
    (comp (ref "T1")
      (value "2SC536F")
      (footprint "eagle-import:TO92")
      (libsource (lib "eagle-import") (part "-NPN-TO92"))
    )
    (comp (ref "T2")
      (value "2SA733P")
      (footprint "eagle-import:TO92")
      (libsource (lib "eagle-import") (part "-PNP-TO92"))
    )
    (comp (ref "T3")
      (value "2SC536F")
      (footprint "eagle-import:TO92")
      (libsource (lib "eagle-import") (part "-NPN-TO92"))
    )
  )
  (nets
    (net (code "1") (name "ACCENT") (class "Default")
      (node (ref "IC4") (pin "19") (pinfunction "[A9/PCINT9]_PC1_19") (pintype "input"))
      (node (ref "R95") (pin "1") (pinfunction "1_1") (pintype "passive"))
    )
    (net (code "2") (name "ACCENT_OUT") (class "Default")
      (node (ref "R97") (pin "1") (pinfunction "1_1") (pintype "passive"))
      (node (ref "T3") (pin "3") (pinfunction "C_3") (pintype "passive"))
    )
    (net (code "3") (name "BUF_1A") (class "Default")
      (node (ref "C2") (pin "+") (pinfunction "+_+") (pintype "passive"))
      (node (ref "D1") (pin "A") (pinfunction "A_A") (pintype "passive"))
      (node (ref "D2") (pin "C") (pinfunction "C_C") (pintype "passive"))
      (node (ref "IC5") (pin "2") (pinfunction "1A_2") (pintype "bidirectional"))
      (node (ref "R24") (pin "1") (pinfunction "1_1") (pintype "passive"))
    )
    (net (code "4") (name "BUF_1Y") (class "Default")
      (node (ref "D2") (pin "A") (pinfunction "A_A") (pintype "passive"))
      (node (ref "IC4") (pin "4") (pinfunction "~{RESET}_4") (pintype "bidirectional"))
      (node (ref "IC5") (pin "3") (pinfunction "1Y_3") (pintype "bidirectional"))
    )
    (net (code "5") (name "BUF_3A") (class "Default")
      (node (ref "IC5") (pin "9") (pinfunction "3A_9") (pintype "bidirectional"))
      (node (ref "IC7") (pin "9") (pinfunction "QH_9") (pintype "output"))
    )
    (net (code "6") (name "CV_OUT") (class "Default")
      (node (ref "IC2") (pin "1") (pinfunction "1OUT_1") (pintype "output"))
      (node (ref "IC3") (pin "4") (pinfunction "SIG_B_IN/OUT_4") (pintype "input"))
      (node (ref "R18") (pin "2") (pinfunction "2_2") (pintype "passive"))
    )
    (net (code "7") (name "GATE") (class "Default")
      (node (ref "IC4") (pin "27") (pinfunction "PE1_[ALE]_27") (pintype "bidirectional"))
      (node (ref "R89") (pin "1") (pinfunction "1_1") (pintype "passive"))
    )
    (net (code "8") (name "GATE_OUT") (class "Default")
      (node (ref "R94") (pin "2") (pinfunction "2_2") (pintype "passive"))
    )
    (net (code "9") (name "GND") (class "Default")
      (node (ref "C1") (pin "2") (pinfunction "2_2") (pintype "passive"))
      (node (ref "C10") (pin "1") (pinfunction "1_1") (pintype "bidirectional"))
      (node (ref "C11") (pin "1") (pinfunction "1_1") (pintype "bidirectional"))
      (node (ref "C13") (pin "1") (pinfunction "1_1") (pintype "bidirectional"))
      (node (ref "C2") (pin "-") (pinfunction "-_-") (pintype "passive"))
      (node (ref "C3") (pin "1") (pinfunction "1_1") (pintype "bidirectional"))
      (node (ref "C4") (pin "1") (pinfunction "1_1") (pintype "bidirectional"))
      (node (ref "C5") (pin "1") (pinfunction "1_1") (pintype "bidirectional"))
      (node (ref "C6") (pin "1") (pinfunction "1_1") (pintype "bidirectional"))
      (node (ref "C7") (pin "1") (pinfunction "1_1") (pintype "bidirectional"))
      (node (ref "C8") (pin "1") (pinfunction "1_1") (pintype "bidirectional"))
      (node (ref "C9") (pin "1") (pinfunction "1_1") (pintype "bidirectional"))
      (node (ref "IC1") (pin "8") (pinfunction "GND_8") (pintype "power_in"))
      (node (ref "IC10") (pin "13") (pinfunction "G_13") (pintype "input"))
      (node (ref "IC11") (pin "10") (pinfunction "SER_10") (pintype "input"))
      (node (ref "IC11") (pin "15") (pinfunction "INH_15") (pintype "input"))
      (node (ref "IC12") (pin "13") (pinfunction "G_13") (pintype "input"))
      (node (ref "IC13") (pin "13") (pinfunction "G_13") (pintype "input"))
      (node (ref "IC14") (pin "13") (pinfunction "G_13") (pintype "input"))
      (node (ref "IC2") (pin "4") (pinfunction "GND_4") (pintype "power_in"))
      (node (ref "IC3") (pin "7") (pinfunction "VSS_7") (pintype "power_in"))
      (node (ref "IC4") (pin "16") (pinfunction "GND_16") (pintype "power_in"))
      (node (ref "IC4") (pin "28") (pinfunction "GND_1_28") (pintype "power_in"))
      (node (ref "IC5") (pin "7") (pinfunction "GND_7") (pintype "bidirectional"))
      (node (ref "IC6") (pin "4") (pinfunction "GND_4") (pintype "power_in"))
      (node (ref "IC7") (pin "15") (pinfunction "INH_15") (pintype "input"))
      (node (ref "IC8") (pin "15") (pinfunction "INH_15") (pintype "input"))
      (node (ref "IC9") (pin "13") (pinfunction "G_13") (pintype "input"))
      (node (ref "LED1") (pin "K") (pinfunction "C_K") (pintype "passive"))
      (node (ref "LED10") (pin "K") (pinfunction "C_K") (pintype "passive"))
      (node (ref "LED11") (pin "K") (pinfunction "C_K") (pintype "passive"))
      (node (ref "LED12") (pin "K") (pinfunction "C_K") (pintype "passive"))
      (node (ref "LED13") (pin "K") (pinfunction "C_K") (pintype "passive"))
      (node (ref "LED14") (pin "K") (pinfunction "C_K") (pintype "passive"))
      (node (ref "LED15") (pin "K") (pinfunction "C_K") (pintype "passive"))
      (node (ref "LED16") (pin "K") (pinfunction "C_K") (pintype "passive"))
      (node (ref "LED2") (pin "K") (pinfunction "C_K") (pintype "passive"))
      (node (ref "LED3") (pin "K") (pinfunction "C_K") (pintype "passive"))
      (node (ref "LED4") (pin "K") (pinfunction "C_K") (pintype "passive"))
      (node (ref "LED5") (pin "K") (pinfunction "C_K") (pintype "passive"))
      (node (ref "LED6") (pin "K") (pinfunction "C_K") (pintype "passive"))
      (node (ref "LED7") (pin "K") (pinfunction "C_K") (pintype "passive"))
      (node (ref "LED8") (pin "K") (pinfunction "C_K") (pintype "passive"))
      (node (ref "LED9") (pin "K") (pinfunction "C_K") (pintype "passive"))
      (node (ref "Q1") (pin "2") (pinfunction "E_2") (pintype "bidirectional"))
      (node (ref "Q2") (pin "2") (pinfunction "E_2") (pintype "bidirectional"))
      (node (ref "Q3") (pin "2") (pinfunction "VSS_2") (pintype "power_in"))
      (node (ref "R17") (pin "1") (pinfunction "1_1") (pintype "passive"))
      (node (ref "R23") (pin "1") (pinfunction "1_1") (pintype "passive"))
      (node (ref "R25") (pin "1") (pinfunction "1_1") (pintype "passive"))
      (node (ref "R26") (pin "1") (pinfunction "1_1") (pintype "passive"))
      (node (ref "R27") (pin "1") (pinfunction "1_1") (pintype "passive"))
      (node (ref "R28") (pin "1") (pinfunction "1_1") (pintype "passive"))
      (node (ref "R29") (pin "1") (pinfunction "1_1") (pintype "passive"))
      (node (ref "R30") (pin "1") (pinfunction "1_1") (pintype "passive"))
      (node (ref "R31") (pin "1") (pinfunction "1_1") (pintype "passive"))
      (node (ref "R32") (pin "1") (pinfunction "1_1") (pintype "passive"))
      (node (ref "R41") (pin "1") (pinfunction "1_1") (pintype "passive"))
      (node (ref "R42") (pin "1") (pinfunction "1_1") (pintype "passive"))
      (node (ref "R43") (pin "1") (pinfunction "1_1") (pintype "passive"))
      (node (ref "R44") (pin "1") (pinfunction "1_1") (pintype "passive"))
      (node (ref "R45") (pin "1") (pinfunction "1_1") (pintype "passive"))
      (node (ref "R46") (pin "1") (pinfunction "1_1") (pintype "passive"))
      (node (ref "R47") (pin "1") (pinfunction "1_1") (pintype "passive"))
      (node (ref "R48") (pin "1") (pinfunction "1_1") (pintype "passive"))
      (node (ref "R57") (pin "1") (pinfunction "1_1") (pintype "passive"))
      (node (ref "R58") (pin "1") (pinfunction "1_1") (pintype "passive"))
      (node (ref "R59") (pin "1") (pinfunction "1_1") (pintype "passive"))
      (node (ref "R60") (pin "1") (pinfunction "1_1") (pintype "passive"))
      (node (ref "R61") (pin "1") (pinfunction "1_1") (pintype "passive"))
      (node (ref "R62") (pin "1") (pinfunction "1_1") (pintype "passive"))
      (node (ref "R63") (pin "1") (pinfunction "1_1") (pintype "passive"))
      (node (ref "R64") (pin "1") (pinfunction "1_1") (pintype "passive"))
      (node (ref "R90") (pin "1") (pinfunction "1_1") (pintype "passive"))
      (node (ref "R93") (pin "1") (pinfunction "1_1") (pintype "passive"))
      (node (ref "R96") (pin "1") (pinfunction "1_1") (pintype "passive"))
      (node (ref "S1") (pin "L1") (pinfunction "L1_L1") (pintype "passive"))
      (node (ref "S10") (pin "L1") (pinfunction "L1_L1") (pintype "passive"))
      (node (ref "S11") (pin "L1") (pinfunction "L1_L1") (pintype "passive"))
      (node (ref "S12") (pin "L1") (pinfunction "L1_L1") (pintype "passive"))
      (node (ref "S13") (pin "L1") (pinfunction "L1_L1") (pintype "passive"))
      (node (ref "S14") (pin "L1") (pinfunction "L1_L1") (pintype "passive"))
      (node (ref "S15") (pin "L1") (pinfunction "L1_L1") (pintype "passive"))
      (node (ref "S16") (pin "L1") (pinfunction "L1_L1") (pintype "passive"))
      (node (ref "S17") (pin "L1") (pinfunction "L1_L1") (pintype "passive"))
      (node (ref "S18") (pin "L1") (pinfunction "L1_L1") (pintype "passive"))
      (node (ref "S19") (pin "L1") (pinfunction "L1_L1") (pintype "passive"))
      (node (ref "S2") (pin "L1") (pinfunction "L1_L1") (pintype "passive"))
      (node (ref "S20") (pin "L1") (pinfunction "L1_L1") (pintype "passive"))
      (node (ref "S21") (pin "L1") (pinfunction "L1_L1") (pintype "passive"))
      (node (ref "S22") (pin "L1") (pinfunction "L1_L1") (pintype "passive"))
      (node (ref "S23") (pin "L1") (pinfunction "L1_L1") (pintype "passive"))
      (node (ref "S24") (pin "L1") (pinfunction "L1_L1") (pintype "passive"))
      (node (ref "S3") (pin "L1") (pinfunction "L1_L1") (pintype "passive"))
      (node (ref "S4") (pin "L1") (pinfunction "L1_L1") (pintype "passive"))
      (node (ref "S5") (pin "L1") (pinfunction "L1_L1") (pintype "passive"))
      (node (ref "S6") (pin "L1") (pinfunction "L1_L1") (pintype "passive"))
      (node (ref "S7") (pin "L1") (pinfunction "L1_L1") (pintype "passive"))
      (node (ref "S8") (pin "L1") (pinfunction "L1_L1") (pintype "passive"))
      (node (ref "S9") (pin "L1") (pinfunction "L1_L1") (pintype "passive"))
      (node (ref "T1") (pin "1") (pinfunction "E_1") (pintype "passive"))
      (node (ref "T3") (pin "1") (pinfunction "E_1") (pintype "passive"))
    )
    (net (code "10") (name "GND_2") (class "Default")
      (node (ref "IC4") (pin "39") (pinfunction "GND_2_39") (pintype "power_in"))
    )
    (net (code "11") (name "LED_LATCH") (class "Default")
      (node (ref "IC10") (pin "12") (pinfunction "RCK_12") (pintype "input"))
      (node (ref "IC12") (pin "12") (pinfunction "RCK_12") (pintype "input"))
      (node (ref "IC13") (pin "12") (pinfunction "RCK_12") (pintype "input"))
      (node (ref "IC14") (pin "12") (pinfunction "RCK_12") (pintype "input"))
      (node (ref "IC4") (pin "30") (pinfunction "PA7_[AD7/PCINT7]_30") (pintype "input"))
      (node (ref "IC9") (pin "12") (pinfunction "RCK_12") (pintype "input"))
    )
    (net (code "12") (name "NOTE0") (class "Default")
      (node (ref "IC1") (pin "11") (pinfunction "4D_11") (pintype "bidirectional"))
      (node (ref "IC4") (pin "20") (pinfunction "[A10/PCINT10]_PC2_20") (pintype "input"))
    )
    (net (code "13") (name "NOTE0Q") (class "Default")
      (node (ref "IC1") (pin "10") (pinfunction "4Q_10") (pintype "bidirectional"))
      (node (ref "R16") (pin "1") (pinfunction "1_1") (pintype "passive"))
    )
    (net (code "14") (name "NOTE1") (class "Default")
      (node (ref "IC1") (pin "6") (pinfunction "3D_6") (pintype "bidirectional"))
      (node (ref "IC4") (pin "21") (pinfunction "[A11/PCINT11]_PC3_21") (pintype "input"))
    )
    (net (code "15") (name "NOTE1Q") (class "Default")
      (node (ref "IC1") (pin "7") (pinfunction "3Q_7") (pintype "bidirectional"))
      (node (ref "R13") (pin "1") (pinfunction "1_1") (pintype "passive"))
    )
    (net (code "16") (name "NOTE2") (class "Default")
      (node (ref "IC1") (pin "13") (pinfunction "5D_13") (pintype "bidirectional"))
      (node (ref "IC4") (pin "22") (pinfunction "[TCK/A12/PCINT12]_PC4_22") (pintype "input"))
    )
    (net (code "17") (name "NOTE2Q") (class "Default")
      (node (ref "IC1") (pin "12") (pinfunction "5Q_12") (pintype "bidirectional"))
      (node (ref "R10") (pin "1") (pinfunction "1_1") (pintype "passive"))
    )
    (net (code "18") (name "NOTE3") (class "Default")
      (node (ref "IC1") (pin "4") (pinfunction "2D_4") (pintype "bidirectional"))
      (node (ref "IC4") (pin "23") (pinfunction "PC5_[A13/TMS/PCINT13]_23") (pintype "input"))
    )
    (net (code "19") (name "NOTE3Q") (class "Default")
      (node (ref "IC1") (pin "5") (pinfunction "2Q_5") (pintype "bidirectional"))
      (node (ref "R7") (pin "1") (pinfunction "1_1") (pintype "passive"))
    )
    (net (code "20") (name "NOTE4") (class "Default")
      (node (ref "IC1") (pin "14") (pinfunction "6D_14") (pintype "bidirectional"))
      (node (ref "IC4") (pin "24") (pinfunction "PC6_[A14/TDO/PCINT14]_24") (pintype "input"))
    )
    (net (code "21") (name "NOTE4Q") (class "Default")
      (node (ref "IC1") (pin "15") (pinfunction "6Q_15") (pintype "bidirectional"))
      (node (ref "R4") (pin "1") (pinfunction "1_1") (pintype "passive"))
    )
    (net (code "22") (name "NOTE5") (class "Default")
      (node (ref "IC1") (pin "3") (pinfunction "1D_3") (pintype "bidirectional"))
      (node (ref "IC4") (pin "25") (pinfunction "PC7_[A15/TDI/PCINT15]_25") (pintype "input"))
    )
    (net (code "23") (name "NOTE5Q") (class "Default")
      (node (ref "IC1") (pin "2") (pinfunction "1Q_2") (pintype "bidirectional"))
      (node (ref "R1") (pin "1") (pinfunction "1_1") (pintype "passive"))
    )
    (net (code "24") (name "NOTE_LATCH") (class "Default")
      (node (ref "IC1") (pin "9") (pinfunction "CLK_9") (pintype "input"))
      (node (ref "IC4") (pin "26") (pinfunction "PE2_[OC1B]_26") (pintype "bidirectional"))
    )
    (net (code "25") (name "Net-(D3-PadC)") (class "Default")
      (node (ref "D3") (pin "C") (pinfunction "C_C") (pintype "passive"))
      (node (ref "R94") (pin "1") (pinfunction "1_1") (pintype "passive"))
    )
    (net (code "26") (name "Net-(IC2-1IN+)") (class "Default")
      (node (ref "IC2") (pin "3") (pinfunction "1IN+_3") (pintype "input"))
      (node (ref "IC3") (pin "1") (pinfunction "SIG_A_IN/OUT_1") (pintype "input"))
      (node (ref "R1") (pin "2") (pinfunction "2_2") (pintype "passive"))
      (node (ref "R2") (pin "2") (pinfunction "2_2") (pintype "passive"))
      (node (ref "R3") (pin "2") (pinfunction "2_2") (pintype "passive"))
    )
    (net (code "27") (name "Net-(IC2-1IN-)") (class "Default")
      (node (ref "IC2") (pin "2") (pinfunction "1IN-_2") (pintype "input"))
      (node (ref "R18") (pin "1") (pinfunction "1_1") (pintype "passive"))
    )
    (net (code "28") (name "Net-(IC3-CONTROL_A)") (class "Default")
      (node (ref "IC3") (pin "13") (pinfunction "CONTROL_A_13") (pintype "input"))
      (node (ref "Q1") (pin "3") (pinfunction "C_3") (pintype "bidirectional"))
      (node (ref "R19") (pin "1") (pinfunction "1_1") (pintype "passive"))
      (node (ref "R21") (pin "2") (pinfunction "2_2") (pintype "passive"))
    )
    (net (code "29") (name "Net-(IC3-CONTROL_B)") (class "Default")
      (node (ref "IC3") (pin "5") (pinfunction "CONTROL_B_5") (pintype "input"))
      (node (ref "Q2") (pin "3") (pinfunction "C_3") (pintype "bidirectional"))
      (node (ref "R20") (pin "1") (pinfunction "1_1") (pintype "passive"))
    )
    (net (code "30") (name "Net-(IC3-SIG_A_OUT{slash}IN)") (class "Default")
      (node (ref "C1") (pin "1") (pinfunction "1_1") (pintype "passive"))
      (node (ref "IC3") (pin "2") (pinfunction "SIG_A_OUT/IN_2") (pintype "output"))
      (node (ref "IC3") (pin "3") (pinfunction "SIG_B_OUT/IN_3") (pintype "output"))
    )
    (net (code "31") (name "Net-(IC4-XTAL1)") (class "Default")
      (node (ref "IC4") (pin "15") (pinfunction "XTAL1_15") (pintype "bidirectional"))
      (node (ref "Q3") (pin "3") (pinfunction "3_3") (pintype "input"))
    )
    (net (code "32") (name "Net-(IC4-XTAL2)") (class "Default")
      (node (ref "IC4") (pin "14") (pinfunction "XTAL2_14") (pintype "bidirectional"))
      (node (ref "Q3") (pin "1") (pinfunction "1_1") (pintype "output"))
    )
    (net (code "33") (name "Net-(IC7A-A)") (class "Default")
      (node (ref "IC7") (pin "11") (pinfunction "A_11") (pintype "input"))
      (node (ref "S8") (pin "2") (pinfunction "2_2") (pintype "passive"))
    )
    (net (code "34") (name "Net-(IC7A-B)") (class "Default")
      (node (ref "IC7") (pin "12") (pinfunction "B_12") (pintype "input"))
      (node (ref "S7") (pin "2") (pinfunction "2_2") (pintype "passive"))
    )
    (net (code "35") (name "Net-(IC7A-C)") (class "Default")
      (node (ref "IC7") (pin "13") (pinfunction "C_13") (pintype "input"))
      (node (ref "S6") (pin "2") (pinfunction "2_2") (pintype "passive"))
    )
    (net (code "36") (name "Net-(IC7A-D)") (class "Default")
      (node (ref "IC7") (pin "14") (pinfunction "D_14") (pintype "input"))
      (node (ref "S5") (pin "2") (pinfunction "2_2") (pintype "passive"))
    )
    (net (code "37") (name "Net-(IC7A-E)") (class "Default")
      (node (ref "IC7") (pin "3") (pinfunction "E_3") (pintype "input"))
      (node (ref "S4") (pin "2") (pinfunction "2_2") (pintype "passive"))
    )
    (net (code "38") (name "Net-(IC7A-F)") (class "Default")
      (node (ref "IC7") (pin "4") (pinfunction "F_4") (pintype "input"))
      (node (ref "S3") (pin "2") (pinfunction "2_2") (pintype "passive"))
    )
    (net (code "39") (name "Net-(IC7A-G)") (class "Default")
      (node (ref "IC7") (pin "5") (pinfunction "G_5") (pintype "input"))
      (node (ref "S2") (pin "2") (pinfunction "2_2") (pintype "passive"))
    )
    (net (code "40") (name "Net-(IC7A-H)") (class "Default")
      (node (ref "IC7") (pin "6") (pinfunction "H_6") (pintype "input"))
      (node (ref "S1") (pin "2") (pinfunction "2_2") (pintype "passive"))
    )
    (net (code "41") (name "Net-(IC7A-SER)") (class "Default")
      (node (ref "IC7") (pin "10") (pinfunction "SER_10") (pintype "input"))
      (node (ref "IC8") (pin "9") (pinfunction "QH_9") (pintype "output"))
    )
    (net (code "42") (name "Net-(IC8A-A)") (class "Default")
      (node (ref "IC8") (pin "11") (pinfunction "A_11") (pintype "input"))
      (node (ref "S16") (pin "2") (pinfunction "2_2") (pintype "passive"))
    )
    (net (code "43") (name "Net-(IC8A-B)") (class "Default")
      (node (ref "IC8") (pin "12") (pinfunction "B_12") (pintype "input"))
      (node (ref "S15") (pin "2") (pinfunction "2_2") (pintype "passive"))
    )
    (net (code "44") (name "Net-(IC8A-C)") (class "Default")
      (node (ref "IC8") (pin "13") (pinfunction "C_13") (pintype "input"))
      (node (ref "S14") (pin "2") (pinfunction "2_2") (pintype "passive"))
    )
    (net (code "45") (name "Net-(IC8A-D)") (class "Default")
      (node (ref "IC8") (pin "14") (pinfunction "D_14") (pintype "input"))
      (node (ref "S13") (pin "2") (pinfunction "2_2") (pintype "passive"))
    )
    (net (code "46") (name "Net-(IC8A-E)") (class "Default")
      (node (ref "IC8") (pin "3") (pinfunction "E_3") (pintype "input"))
      (node (ref "S12") (pin "2") (pinfunction "2_2") (pintype "passive"))
    )
    (net (code "47") (name "Net-(IC8A-F)") (class "Default")
      (node (ref "IC8") (pin "4") (pinfunction "F_4") (pintype "input"))
      (node (ref "S11") (pin "2") (pinfunction "2_2") (pintype "passive"))
    )
    (net (code "48") (name "Net-(IC8A-G)") (class "Default")
      (node (ref "IC8") (pin "5") (pinfunction "G_5") (pintype "input"))
      (node (ref "S10") (pin "2") (pinfunction "2_2") (pintype "passive"))
    )
    (net (code "49") (name "Net-(IC8A-H)") (class "Default")
      (node (ref "IC8") (pin "6") (pinfunction "H_6") (pintype "input"))
      (node (ref "S9") (pin "2") (pinfunction "2_2") (pintype "passive"))
    )
    (net (code "50") (name "Net-(IC9A-QA)") (class "Default")
      (node (ref "IC9") (pin "15") (pinfunction "QA_15") (pintype "tri_state"))
      (node (ref "R49") (pin "1") (pinfunction "1_1") (pintype "passive"))
    )
    (net (code "51") (name "Net-(IC9A-QB)") (class "Default")
      (node (ref "IC9") (pin "1") (pinfunction "QB_1") (pintype "tri_state"))
      (node (ref "R50") (pin "1") (pinfunction "1_1") (pintype "passive"))
    )
    (net (code "52") (name "Net-(IC9A-QC)") (class "Default")
      (node (ref "IC9") (pin "2") (pinfunction "QC_2") (pintype "tri_state"))
      (node (ref "R51") (pin "1") (pinfunction "1_1") (pintype "passive"))
    )
    (net (code "53") (name "Net-(IC9A-QD)") (class "Default")
      (node (ref "IC9") (pin "3") (pinfunction "QD_3") (pintype "tri_state"))
      (node (ref "R52") (pin "1") (pinfunction "1_1") (pintype "passive"))
    )
    (net (code "54") (name "Net-(IC9A-QE)") (class "Default")
      (node (ref "IC9") (pin "4") (pinfunction "QE_4") (pintype "tri_state"))
      (node (ref "R53") (pin "1") (pinfunction "1_1") (pintype "passive"))
    )
    (net (code "55") (name "Net-(IC9A-QF)") (class "Default")
      (node (ref "IC9") (pin "5") (pinfunction "QF_5") (pintype "tri_state"))
      (node (ref "R54") (pin "1") (pinfunction "1_1") (pintype "passive"))
    )
    (net (code "56") (name "Net-(IC9A-QG)") (class "Default")
      (node (ref "IC9") (pin "6") (pinfunction "QG_6") (pintype "tri_state"))
      (node (ref "R55") (pin "1") (pinfunction "1_1") (pintype "passive"))
    )
    (net (code "57") (name "Net-(IC9A-QH)") (class "Default")
      (node (ref "IC9") (pin "7") (pinfunction "QH_7") (pintype "tri_state"))
      (node (ref "R56") (pin "1") (pinfunction "1_1") (pintype "passive"))
    )
    (net (code "58") (name "Net-(IC10A-QA)") (class "Default")
      (node (ref "IC10") (pin "15") (pinfunction "QA_15") (pintype "tri_state"))
      (node (ref "R33") (pin "1") (pinfunction "1_1") (pintype "passive"))
    )
    (net (code "59") (name "Net-(IC10A-QB)") (class "Default")
      (node (ref "IC10") (pin "1") (pinfunction "QB_1") (pintype "tri_state"))
      (node (ref "R34") (pin "1") (pinfunction "1_1") (pintype "passive"))
    )
    (net (code "60") (name "Net-(IC10A-QC)") (class "Default")
      (node (ref "IC10") (pin "2") (pinfunction "QC_2") (pintype "tri_state"))
      (node (ref "R35") (pin "1") (pinfunction "1_1") (pintype "passive"))
    )
    (net (code "61") (name "Net-(IC10A-QD)") (class "Default")
      (node (ref "IC10") (pin "3") (pinfunction "QD_3") (pintype "tri_state"))
      (node (ref "R36") (pin "1") (pinfunction "1_1") (pintype "passive"))
    )
    (net (code "62") (name "Net-(IC10A-QE)") (class "Default")
      (node (ref "IC10") (pin "4") (pinfunction "QE_4") (pintype "tri_state"))
      (node (ref "R37") (pin "1") (pinfunction "1_1") (pintype "passive"))
    )
    (net (code "63") (name "Net-(IC10A-QF)") (class "Default")
      (node (ref "IC10") (pin "5") (pinfunction "QF_5") (pintype "tri_state"))
      (node (ref "R38") (pin "1") (pinfunction "1_1") (pintype "passive"))
    )
    (net (code "64") (name "Net-(IC10A-QG)") (class "Default")
      (node (ref "IC10") (pin "6") (pinfunction "QG_6") (pintype "tri_state"))
      (node (ref "R39") (pin "1") (pinfunction "1_1") (pintype "passive"))
    )
    (net (code "65") (name "Net-(IC10A-QH)") (class "Default")
      (node (ref "IC10") (pin "7") (pinfunction "QH_7") (pintype "tri_state"))
      (node (ref "R40") (pin "1") (pinfunction "1_1") (pintype "passive"))
    )
    (net (code "66") (name "Net-(IC11A-A)") (class "Default")
      (node (ref "IC11") (pin "11") (pinfunction "A_11") (pintype "input"))
      (node (ref "S24") (pin "2") (pinfunction "2_2") (pintype "passive"))
    )
    (net (code "67") (name "Net-(IC11A-B)") (class "Default")
      (node (ref "IC11") (pin "12") (pinfunction "B_12") (pintype "input"))
      (node (ref "S23") (pin "2") (pinfunction "2_2") (pintype "passive"))
    )
    (net (code "68") (name "Net-(IC11A-C)") (class "Default")
      (node (ref "IC11") (pin "13") (pinfunction "C_13") (pintype "input"))
      (node (ref "S22") (pin "2") (pinfunction "2_2") (pintype "passive"))
    )
    (net (code "69") (name "Net-(IC11A-D)") (class "Default")
      (node (ref "IC11") (pin "14") (pinfunction "D_14") (pintype "input"))
      (node (ref "S21") (pin "2") (pinfunction "2_2") (pintype "passive"))
    )
    (net (code "70") (name "Net-(IC11A-E)") (class "Default")
      (node (ref "IC11") (pin "3") (pinfunction "E_3") (pintype "input"))
      (node (ref "S20") (pin "2") (pinfunction "2_2") (pintype "passive"))
    )
    (net (code "71") (name "Net-(IC11A-F)") (class "Default")
      (node (ref "IC11") (pin "4") (pinfunction "F_4") (pintype "input"))
      (node (ref "S19") (pin "2") (pinfunction "2_2") (pintype "passive"))
    )
    (net (code "72") (name "Net-(IC11A-G)") (class "Default")
      (node (ref "IC11") (pin "5") (pinfunction "G_5") (pintype "input"))
      (node (ref "S18") (pin "2") (pinfunction "2_2") (pintype "passive"))
    )
    (net (code "73") (name "Net-(IC11A-H)") (class "Default")
      (node (ref "IC11") (pin "6") (pinfunction "H_6") (pintype "input"))
      (node (ref "S17") (pin "2") (pinfunction "2_2") (pintype "passive"))
    )
    (net (code "74") (name "Net-(IC11A-QH)") (class "Default")
      (node (ref "IC11") (pin "9") (pinfunction "QH_9") (pintype "output"))
      (node (ref "IC8") (pin "10") (pinfunction "SER_10") (pintype "input"))
    )
    (net (code "75") (name "Net-(IC12A-QA)") (class "Default")
      (node (ref "IC12") (pin "15") (pinfunction "QA_15") (pintype "tri_state"))
      (node (ref "R65") (pin "1") (pinfunction "1_1") (pintype "passive"))
    )
    (net (code "76") (name "Net-(IC12A-QB)") (class "Default")
      (node (ref "IC12") (pin "1") (pinfunction "QB_1") (pintype "tri_state"))
      (node (ref "R66") (pin "1") (pinfunction "1_1") (pintype "passive"))
    )
    (net (code "77") (name "Net-(IC12A-QC)") (class "Default")
      (node (ref "IC12") (pin "2") (pinfunction "QC_2") (pintype "tri_state"))
      (node (ref "R67") (pin "1") (pinfunction "1_1") (pintype "passive"))
    )
    (net (code "78") (name "Net-(IC12A-QD)") (class "Default")
      (node (ref "IC12") (pin "3") (pinfunction "QD_3") (pintype "tri_state"))
      (node (ref "R68") (pin "1") (pinfunction "1_1") (pintype "passive"))
    )
    (net (code "79") (name "Net-(IC12A-QE)") (class "Default")
      (node (ref "IC12") (pin "4") (pinfunction "QE_4") (pintype "tri_state"))
      (node (ref "R69") (pin "1") (pinfunction "1_1") (pintype "passive"))
    )
    (net (code "80") (name "Net-(IC12A-QF)") (class "Default")
      (node (ref "IC12") (pin "5") (pinfunction "QF_5") (pintype "tri_state"))
      (node (ref "R70") (pin "1") (pinfunction "1_1") (pintype "passive"))
    )
    (net (code "81") (name "Net-(IC12A-QG)") (class "Default")
      (node (ref "IC12") (pin "6") (pinfunction "QG_6") (pintype "tri_state"))
      (node (ref "R71") (pin "1") (pinfunction "1_1") (pintype "passive"))
    )
    (net (code "82") (name "Net-(IC12A-QH)") (class "Default")
      (node (ref "IC12") (pin "7") (pinfunction "QH_7") (pintype "tri_state"))
      (node (ref "R72") (pin "1") (pinfunction "1_1") (pintype "passive"))
    )
    (net (code "83") (name "Net-(IC13A-QA)") (class "Default")
      (node (ref "IC13") (pin "15") (pinfunction "QA_15") (pintype "tri_state"))
      (node (ref "R73") (pin "1") (pinfunction "1_1") (pintype "passive"))
    )
    (net (code "84") (name "Net-(IC13A-QB)") (class "Default")
      (node (ref "IC13") (pin "1") (pinfunction "QB_1") (pintype "tri_state"))
      (node (ref "R74") (pin "1") (pinfunction "1_1") (pintype "passive"))
    )
    (net (code "85") (name "Net-(IC13A-QC)") (class "Default")
      (node (ref "IC13") (pin "2") (pinfunction "QC_2") (pintype "tri_state"))
      (node (ref "R75") (pin "1") (pinfunction "1_1") (pintype "passive"))
    )
    (net (code "86") (name "Net-(IC13A-QD)") (class "Default")
      (node (ref "IC13") (pin "3") (pinfunction "QD_3") (pintype "tri_state"))
      (node (ref "R76") (pin "1") (pinfunction "1_1") (pintype "passive"))
    )
    (net (code "87") (name "Net-(IC13A-QE)") (class "Default")
      (node (ref "IC13") (pin "4") (pinfunction "QE_4") (pintype "tri_state"))
      (node (ref "R77") (pin "1") (pinfunction "1_1") (pintype "passive"))
    )
    (net (code "88") (name "Net-(IC13A-QF)") (class "Default")
      (node (ref "IC13") (pin "5") (pinfunction "QF_5") (pintype "tri_state"))
      (node (ref "R78") (pin "1") (pinfunction "1_1") (pintype "passive"))
    )
    (net (code "89") (name "Net-(IC13A-QG)") (class "Default")
      (node (ref "IC13") (pin "6") (pinfunction "QG_6") (pintype "tri_state"))
      (node (ref "R79") (pin "1") (pinfunction "1_1") (pintype "passive"))
    )
    (net (code "90") (name "Net-(IC13A-QH)") (class "Default")
      (node (ref "IC13") (pin "7") (pinfunction "QH_7") (pintype "tri_state"))
      (node (ref "R80") (pin "1") (pinfunction "1_1") (pintype "passive"))
    )
    (net (code "91") (name "Net-(IC14A-QA)") (class "Default")
      (node (ref "IC14") (pin "15") (pinfunction "QA_15") (pintype "tri_state"))
      (node (ref "R81") (pin "1") (pinfunction "1_1") (pintype "passive"))
    )
    (net (code "92") (name "Net-(IC14A-QB)") (class "Default")
      (node (ref "IC14") (pin "1") (pinfunction "QB_1") (pintype "tri_state"))
      (node (ref "R82") (pin "1") (pinfunction "1_1") (pintype "passive"))
    )
    (net (code "93") (name "Net-(IC14A-QC)") (class "Default")
      (node (ref "IC14") (pin "2") (pinfunction "QC_2") (pintype "tri_state"))
      (node (ref "R83") (pin "1") (pinfunction "1_1") (pintype "passive"))
    )
    (net (code "94") (name "Net-(IC14A-QD)") (class "Default")
      (node (ref "IC14") (pin "3") (pinfunction "QD_3") (pintype "tri_state"))
      (node (ref "R84") (pin "1") (pinfunction "1_1") (pintype "passive"))
    )
    (net (code "95") (name "Net-(IC14A-QE)") (class "Default")
      (node (ref "IC14") (pin "4") (pinfunction "QE_4") (pintype "tri_state"))
      (node (ref "R85") (pin "1") (pinfunction "1_1") (pintype "passive"))
    )
    (net (code "96") (name "Net-(IC14A-QF)") (class "Default")
      (node (ref "IC14") (pin "5") (pinfunction "QF_5") (pintype "tri_state"))
      (node (ref "R86") (pin "1") (pinfunction "1_1") (pintype "passive"))
    )
    (net (code "97") (name "Net-(IC14A-QG)") (class "Default")
      (node (ref "IC14") (pin "6") (pinfunction "QG_6") (pintype "tri_state"))
      (node (ref "R87") (pin "1") (pinfunction "1_1") (pintype "passive"))
    )
    (net (code "98") (name "Net-(IC14A-QH)") (class "Default")
      (node (ref "IC14") (pin "7") (pinfunction "QH_7") (pintype "tri_state"))
      (node (ref "R88") (pin "1") (pinfunction "1_1") (pintype "passive"))
    )
    (net (code "99") (name "Net-(LED1-PadA)") (class "Default")
      (node (ref "LED1") (pin "A") (pinfunction "A_A") (pintype "passive"))
      (node (ref "R73") (pin "2") (pinfunction "2_2") (pintype "passive"))
    )
    (net (code "100") (name "Net-(LED2-PadA)") (class "Default")
      (node (ref "LED2") (pin "A") (pinfunction "A_A") (pintype "passive"))
      (node (ref "R74") (pin "2") (pinfunction "2_2") (pintype "passive"))
    )
    (net (code "101") (name "Net-(LED3-PadA)") (class "Default")
      (node (ref "LED3") (pin "A") (pinfunction "A_A") (pintype "passive"))
      (node (ref "R75") (pin "2") (pinfunction "2_2") (pintype "passive"))
    )
    (net (code "102") (name "Net-(LED4-PadA)") (class "Default")
      (node (ref "LED4") (pin "A") (pinfunction "A_A") (pintype "passive"))
      (node (ref "R76") (pin "2") (pinfunction "2_2") (pintype "passive"))
    )
    (net (code "103") (name "Net-(LED5-PadA)") (class "Default")
      (node (ref "LED5") (pin "A") (pinfunction "A_A") (pintype "passive"))
      (node (ref "R77") (pin "2") (pinfunction "2_2") (pintype "passive"))
    )
    (net (code "104") (name "Net-(LED6-PadA)") (class "Default")
      (node (ref "LED6") (pin "A") (pinfunction "A_A") (pintype "passive"))
      (node (ref "R78") (pin "2") (pinfunction "2_2") (pintype "passive"))
    )
    (net (code "105") (name "Net-(LED7-PadA)") (class "Default")
      (node (ref "LED7") (pin "A") (pinfunction "A_A") (pintype "passive"))
      (node (ref "R79") (pin "2") (pinfunction "2_2") (pintype "passive"))
    )
    (net (code "106") (name "Net-(LED8-PadA)") (class "Default")
      (node (ref "LED8") (pin "A") (pinfunction "A_A") (pintype "passive"))
      (node (ref "R80") (pin "2") (pinfunction "2_2") (pintype "passive"))
    )
    (net (code "107") (name "Net-(LED9-PadA)") (class "Default")
      (node (ref "LED9") (pin "A") (pinfunction "A_A") (pintype "passive"))
      (node (ref "R81") (pin "2") (pinfunction "2_2") (pintype "passive"))
    )
    (net (code "108") (name "Net-(LED10-PadA)") (class "Default")
      (node (ref "LED10") (pin "A") (pinfunction "A_A") (pintype "passive"))
      (node (ref "R82") (pin "2") (pinfunction "2_2") (pintype "passive"))
    )
    (net (code "109") (name "Net-(LED11-PadA)") (class "Default")
      (node (ref "LED11") (pin "A") (pinfunction "A_A") (pintype "passive"))
      (node (ref "R83") (pin "2") (pinfunction "2_2") (pintype "passive"))
    )
    (net (code "110") (name "Net-(LED12-PadA)") (class "Default")
      (node (ref "LED12") (pin "A") (pinfunction "A_A") (pintype "passive"))
      (node (ref "R84") (pin "2") (pinfunction "2_2") (pintype "passive"))
    )
    (net (code "111") (name "Net-(LED13-PadA)") (class "Default")
      (node (ref "LED13") (pin "A") (pinfunction "A_A") (pintype "passive"))
      (node (ref "R85") (pin "2") (pinfunction "2_2") (pintype "passive"))
    )
    (net (code "112") (name "Net-(LED14-PadA)") (class "Default")
      (node (ref "LED14") (pin "A") (pinfunction "A_A") (pintype "passive"))
      (node (ref "R86") (pin "2") (pinfunction "2_2") (pintype "passive"))
    )
    (net (code "113") (name "Net-(LED15-PadA)") (class "Default")
      (node (ref "LED15") (pin "A") (pinfunction "A_A") (pintype "passive"))
      (node (ref "R87") (pin "2") (pinfunction "2_2") (pintype "passive"))
    )
    (net (code "114") (name "Net-(LED16-PadA)") (class "Default")
      (node (ref "LED16") (pin "A") (pinfunction "A_A") (pintype "passive"))
      (node (ref "R88") (pin "2") (pinfunction "2_2") (pintype "passive"))
    )
    (net (code "115") (name "Net-(Q1-B)") (class "Default")
      (node (ref "Q1") (pin "1") (pinfunction "B_1") (pintype "bidirectional"))
      (node (ref "R22") (pin "2") (pinfunction "2_2") (pintype "passive"))
      (node (ref "R23") (pin "2") (pinfunction "2_2") (pintype "passive"))
    )
    (net (code "116") (name "Net-(Q2-B)") (class "Default")
      (node (ref "Q2") (pin "1") (pinfunction "B_1") (pintype "bidirectional"))
      (node (ref "R21") (pin "1") (pinfunction "1_1") (pintype "passive"))
    )
    (net (code "117") (name "Net-(R2-Pad1)") (class "Default")
      (node (ref "R2") (pin "1") (pinfunction "1_1") (pintype "passive"))
      (node (ref "R3") (pin "1") (pinfunction "1_1") (pintype "passive"))
      (node (ref "R4") (pin "2") (pinfunction "2_2") (pintype "passive"))
      (node (ref "R5") (pin "2") (pinfunction "2_2") (pintype "passive"))
      (node (ref "R6") (pin "2") (pinfunction "2_2") (pintype "passive"))
    )
    (net (code "118") (name "Net-(R5-Pad1)") (class "Default")
      (node (ref "R5") (pin "1") (pinfunction "1_1") (pintype "passive"))
      (node (ref "R6") (pin "1") (pinfunction "1_1") (pintype "passive"))
      (node (ref "R7") (pin "2") (pinfunction "2_2") (pintype "passive"))
      (node (ref "R8") (pin "2") (pinfunction "2_2") (pintype "passive"))
      (node (ref "R9") (pin "2") (pinfunction "2_2") (pintype "passive"))
    )
    (net (code "119") (name "Net-(R10-Pad2)") (class "Default")
      (node (ref "R10") (pin "2") (pinfunction "2_2") (pintype "passive"))
      (node (ref "R11") (pin "2") (pinfunction "2_2") (pintype "passive"))
      (node (ref "R12") (pin "2") (pinfunction "2_2") (pintype "passive"))
      (node (ref "R8") (pin "1") (pinfunction "1_1") (pintype "passive"))
      (node (ref "R9") (pin "1") (pinfunction "1_1") (pintype "passive"))
    )
    (net (code "120") (name "Net-(R11-Pad1)") (class "Default")
      (node (ref "R11") (pin "1") (pinfunction "1_1") (pintype "passive"))
      (node (ref "R12") (pin "1") (pinfunction "1_1") (pintype "passive"))
      (node (ref "R13") (pin "2") (pinfunction "2_2") (pintype "passive"))
      (node (ref "R14") (pin "2") (pinfunction "2_2") (pintype "passive"))
      (node (ref "R15") (pin "2") (pinfunction "2_2") (pintype "passive"))
    )
    (net (code "121") (name "Net-(R14-Pad1)") (class "Default")
      (node (ref "R14") (pin "1") (pinfunction "1_1") (pintype "passive"))
      (node (ref "R15") (pin "1") (pinfunction "1_1") (pintype "passive"))
      (node (ref "R16") (pin "2") (pinfunction "2_2") (pintype "passive"))
      (node (ref "R17") (pin "2") (pinfunction "2_2") (pintype "passive"))
    )
    (net (code "122") (name "Net-(R25-Pad2)") (class "Default")
      (node (ref "R25") (pin "2") (pinfunction "2_2") (pintype "passive"))
      (node (ref "S1") (pin "1") (pinfunction "1_1") (pintype "passive"))
    )
    (net (code "123") (name "Net-(R26-Pad2)") (class "Default")
      (node (ref "R26") (pin "2") (pinfunction "2_2") (pintype "passive"))
      (node (ref "S2") (pin "1") (pinfunction "1_1") (pintype "passive"))
    )
    (net (code "124") (name "Net-(R27-Pad2)") (class "Default")
      (node (ref "R27") (pin "2") (pinfunction "2_2") (pintype "passive"))
      (node (ref "S3") (pin "1") (pinfunction "1_1") (pintype "passive"))
    )
    (net (code "125") (name "Net-(R28-Pad2)") (class "Default")
      (node (ref "R28") (pin "2") (pinfunction "2_2") (pintype "passive"))
      (node (ref "S4") (pin "1") (pinfunction "1_1") (pintype "passive"))
    )
    (net (code "126") (name "Net-(R29-Pad2)") (class "Default")
      (node (ref "R29") (pin "2") (pinfunction "2_2") (pintype "passive"))
      (node (ref "S5") (pin "1") (pinfunction "1_1") (pintype "passive"))
    )
    (net (code "127") (name "Net-(R30-Pad2)") (class "Default")
      (node (ref "R30") (pin "2") (pinfunction "2_2") (pintype "passive"))
      (node (ref "S6") (pin "1") (pinfunction "1_1") (pintype "passive"))
    )
    (net (code "128") (name "Net-(R31-Pad2)") (class "Default")
      (node (ref "R31") (pin "2") (pinfunction "2_2") (pintype "passive"))
      (node (ref "S7") (pin "1") (pinfunction "1_1") (pintype "passive"))
    )
    (net (code "129") (name "Net-(R32-Pad2)") (class "Default")
      (node (ref "R32") (pin "2") (pinfunction "2_2") (pintype "passive"))
      (node (ref "S8") (pin "1") (pinfunction "1_1") (pintype "passive"))
    )
    (net (code "130") (name "Net-(R33-Pad2)") (class "Default")
      (node (ref "R33") (pin "2") (pinfunction "2_2") (pintype "passive"))
      (node (ref "S1") (pin "L2") (pinfunction "L2_L2") (pintype "passive"))
    )
    (net (code "131") (name "Net-(R34-Pad2)") (class "Default")
      (node (ref "R34") (pin "2") (pinfunction "2_2") (pintype "passive"))
      (node (ref "S2") (pin "L2") (pinfunction "L2_L2") (pintype "passive"))
    )
    (net (code "132") (name "Net-(R35-Pad2)") (class "Default")
      (node (ref "R35") (pin "2") (pinfunction "2_2") (pintype "passive"))
      (node (ref "S3") (pin "L2") (pinfunction "L2_L2") (pintype "passive"))
    )
    (net (code "133") (name "Net-(R36-Pad2)") (class "Default")
      (node (ref "R36") (pin "2") (pinfunction "2_2") (pintype "passive"))
      (node (ref "S4") (pin "L2") (pinfunction "L2_L2") (pintype "passive"))
    )
    (net (code "134") (name "Net-(R37-Pad2)") (class "Default")
      (node (ref "R37") (pin "2") (pinfunction "2_2") (pintype "passive"))
      (node (ref "S5") (pin "L2") (pinfunction "L2_L2") (pintype "passive"))
    )
    (net (code "135") (name "Net-(R38-Pad2)") (class "Default")
      (node (ref "R38") (pin "2") (pinfunction "2_2") (pintype "passive"))
      (node (ref "S6") (pin "L2") (pinfunction "L2_L2") (pintype "passive"))
    )
    (net (code "136") (name "Net-(R39-Pad2)") (class "Default")
      (node (ref "R39") (pin "2") (pinfunction "2_2") (pintype "passive"))
      (node (ref "S7") (pin "L2") (pinfunction "L2_L2") (pintype "passive"))
    )
    (net (code "137") (name "Net-(R40-Pad2)") (class "Default")
      (node (ref "R40") (pin "2") (pinfunction "2_2") (pintype "passive"))
      (node (ref "S8") (pin "L2") (pinfunction "L2_L2") (pintype "passive"))
    )
    (net (code "138") (name "Net-(R41-Pad2)") (class "Default")
      (node (ref "R41") (pin "2") (pinfunction "2_2") (pintype "passive"))
      (node (ref "S9") (pin "1") (pinfunction "1_1") (pintype "passive"))
    )
    (net (code "139") (name "Net-(R42-Pad2)") (class "Default")
      (node (ref "R42") (pin "2") (pinfunction "2_2") (pintype "passive"))
      (node (ref "S10") (pin "1") (pinfunction "1_1") (pintype "passive"))
    )
    (net (code "140") (name "Net-(R43-Pad2)") (class "Default")
      (node (ref "R43") (pin "2") (pinfunction "2_2") (pintype "passive"))
      (node (ref "S11") (pin "1") (pinfunction "1_1") (pintype "passive"))
    )
    (net (code "141") (name "Net-(R44-Pad2)") (class "Default")
      (node (ref "R44") (pin "2") (pinfunction "2_2") (pintype "passive"))
      (node (ref "S12") (pin "1") (pinfunction "1_1") (pintype "passive"))
    )
    (net (code "142") (name "Net-(R45-Pad2)") (class "Default")
      (node (ref "R45") (pin "2") (pinfunction "2_2") (pintype "passive"))
      (node (ref "S13") (pin "1") (pinfunction "1_1") (pintype "passive"))
    )
    (net (code "143") (name "Net-(R46-Pad2)") (class "Default")
      (node (ref "R46") (pin "2") (pinfunction "2_2") (pintype "passive"))
      (node (ref "S14") (pin "1") (pinfunction "1_1") (pintype "passive"))
    )
    (net (code "144") (name "Net-(R47-Pad2)") (class "Default")
      (node (ref "R47") (pin "2") (pinfunction "2_2") (pintype "passive"))
      (node (ref "S15") (pin "1") (pinfunction "1_1") (pintype "passive"))
    )
    (net (code "145") (name "Net-(R48-Pad2)") (class "Default")
      (node (ref "R48") (pin "2") (pinfunction "2_2") (pintype "passive"))
      (node (ref "S16") (pin "1") (pinfunction "1_1") (pintype "passive"))
    )
    (net (code "146") (name "Net-(R49-Pad2)") (class "Default")
      (node (ref "R49") (pin "2") (pinfunction "2_2") (pintype "passive"))
      (node (ref "S9") (pin "L2") (pinfunction "L2_L2") (pintype "passive"))
    )
    (net (code "147") (name "Net-(R50-Pad2)") (class "Default")
      (node (ref "R50") (pin "2") (pinfunction "2_2") (pintype "passive"))
      (node (ref "S10") (pin "L2") (pinfunction "L2_L2") (pintype "passive"))
    )
    (net (code "148") (name "Net-(R51-Pad2)") (class "Default")
      (node (ref "R51") (pin "2") (pinfunction "2_2") (pintype "passive"))
      (node (ref "S11") (pin "L2") (pinfunction "L2_L2") (pintype "passive"))
    )
    (net (code "149") (name "Net-(R52-Pad2)") (class "Default")
      (node (ref "R52") (pin "2") (pinfunction "2_2") (pintype "passive"))
      (node (ref "S12") (pin "L2") (pinfunction "L2_L2") (pintype "passive"))
    )
    (net (code "150") (name "Net-(R53-Pad2)") (class "Default")
      (node (ref "R53") (pin "2") (pinfunction "2_2") (pintype "passive"))
      (node (ref "S13") (pin "L2") (pinfunction "L2_L2") (pintype "passive"))
    )
    (net (code "151") (name "Net-(R54-Pad2)") (class "Default")
      (node (ref "R54") (pin "2") (pinfunction "2_2") (pintype "passive"))
      (node (ref "S14") (pin "L2") (pinfunction "L2_L2") (pintype "passive"))
    )
    (net (code "152") (name "Net-(R55-Pad2)") (class "Default")
      (node (ref "R55") (pin "2") (pinfunction "2_2") (pintype "passive"))
      (node (ref "S15") (pin "L2") (pinfunction "L2_L2") (pintype "passive"))
    )
    (net (code "153") (name "Net-(R56-Pad2)") (class "Default")
      (node (ref "R56") (pin "2") (pinfunction "2_2") (pintype "passive"))
      (node (ref "S16") (pin "L2") (pinfunction "L2_L2") (pintype "passive"))
    )
    (net (code "154") (name "Net-(R57-Pad2)") (class "Default")
      (node (ref "R57") (pin "2") (pinfunction "2_2") (pintype "passive"))
      (node (ref "S17") (pin "1") (pinfunction "1_1") (pintype "passive"))
    )
    (net (code "155") (name "Net-(R58-Pad2)") (class "Default")
      (node (ref "R58") (pin "2") (pinfunction "2_2") (pintype "passive"))
      (node (ref "S18") (pin "1") (pinfunction "1_1") (pintype "passive"))
    )
    (net (code "156") (name "Net-(R59-Pad2)") (class "Default")
      (node (ref "R59") (pin "2") (pinfunction "2_2") (pintype "passive"))
      (node (ref "S19") (pin "1") (pinfunction "1_1") (pintype "passive"))
    )
    (net (code "157") (name "Net-(R60-Pad2)") (class "Default")
      (node (ref "R60") (pin "2") (pinfunction "2_2") (pintype "passive"))
      (node (ref "S20") (pin "1") (pinfunction "1_1") (pintype "passive"))
    )
    (net (code "158") (name "Net-(R61-Pad2)") (class "Default")
      (node (ref "R61") (pin "2") (pinfunction "2_2") (pintype "passive"))
      (node (ref "S21") (pin "1") (pinfunction "1_1") (pintype "passive"))
    )
    (net (code "159") (name "Net-(R62-Pad2)") (class "Default")
      (node (ref "R62") (pin "2") (pinfunction "2_2") (pintype "passive"))
      (node (ref "S22") (pin "1") (pinfunction "1_1") (pintype "passive"))
    )
    (net (code "160") (name "Net-(R63-Pad2)") (class "Default")
      (node (ref "R63") (pin "2") (pinfunction "2_2") (pintype "passive"))
      (node (ref "S23") (pin "1") (pinfunction "1_1") (pintype "passive"))
    )
    (net (code "161") (name "Net-(R64-Pad2)") (class "Default")
      (node (ref "R64") (pin "2") (pinfunction "2_2") (pintype "passive"))
      (node (ref "S24") (pin "1") (pinfunction "1_1") (pintype "passive"))
    )
    (net (code "162") (name "Net-(R65-Pad2)") (class "Default")
      (node (ref "R65") (pin "2") (pinfunction "2_2") (pintype "passive"))
      (node (ref "S17") (pin "L2") (pinfunction "L2_L2") (pintype "passive"))
    )
    (net (code "163") (name "Net-(R66-Pad2)") (class "Default")
      (node (ref "R66") (pin "2") (pinfunction "2_2") (pintype "passive"))
      (node (ref "S18") (pin "L2") (pinfunction "L2_L2") (pintype "passive"))
    )
    (net (code "164") (name "Net-(R67-Pad2)") (class "Default")
      (node (ref "R67") (pin "2") (pinfunction "2_2") (pintype "passive"))
      (node (ref "S19") (pin "L2") (pinfunction "L2_L2") (pintype "passive"))
    )
    (net (code "165") (name "Net-(R68-Pad2)") (class "Default")
      (node (ref "R68") (pin "2") (pinfunction "2_2") (pintype "passive"))
      (node (ref "S20") (pin "L2") (pinfunction "L2_L2") (pintype "passive"))
    )
    (net (code "166") (name "Net-(R69-Pad2)") (class "Default")
      (node (ref "R69") (pin "2") (pinfunction "2_2") (pintype "passive"))
      (node (ref "S21") (pin "L2") (pinfunction "L2_L2") (pintype "passive"))
    )
    (net (code "167") (name "Net-(R70-Pad2)") (class "Default")
      (node (ref "R70") (pin "2") (pinfunction "2_2") (pintype "passive"))
      (node (ref "S22") (pin "L2") (pinfunction "L2_L2") (pintype "passive"))
    )
    (net (code "168") (name "Net-(R71-Pad2)") (class "Default")
      (node (ref "R71") (pin "2") (pinfunction "2_2") (pintype "passive"))
      (node (ref "S23") (pin "L2") (pinfunction "L2_L2") (pintype "passive"))
    )
    (net (code "169") (name "Net-(R72-Pad2)") (class "Default")
      (node (ref "R72") (pin "2") (pinfunction "2_2") (pintype "passive"))
      (node (ref "S24") (pin "L2") (pinfunction "L2_L2") (pintype "passive"))
    )
    (net (code "170") (name "Net-(T1-B)") (class "Default")
      (node (ref "R89") (pin "2") (pinfunction "2_2") (pintype "passive"))
      (node (ref "R90") (pin "2") (pinfunction "2_2") (pintype "passive"))
      (node (ref "T1") (pin "2") (pinfunction "B_2") (pintype "passive"))
    )
    (net (code "171") (name "Net-(T1-C)") (class "Default")
      (node (ref "R91") (pin "1") (pinfunction "1_1") (pintype "passive"))
      (node (ref "T1") (pin "3") (pinfunction "C_3") (pintype "passive"))
    )
    (net (code "172") (name "Net-(T2-B)") (class "Default")
      (node (ref "C12") (pin "-") (pinfunction "-_-") (pintype "passive"))
      (node (ref "R91") (pin "2") (pinfunction "2_2") (pintype "passive"))
      (node (ref "R92") (pin "1") (pinfunction "1_1") (pintype "passive"))
      (node (ref "T2") (pin "2") (pinfunction "B_2") (pintype "passive"))
    )
    (net (code "173") (name "Net-(T2-C)") (class "Default")
      (node (ref "D3") (pin "A") (pinfunction "A_A") (pintype "passive"))
      (node (ref "R93") (pin "2") (pinfunction "2_2") (pintype "passive"))
      (node (ref "T2") (pin "3") (pinfunction "C_3") (pintype "passive"))
    )
    (net (code "174") (name "Net-(T3-B)") (class "Default")
      (node (ref "R95") (pin "2") (pinfunction "2_2") (pintype "passive"))
      (node (ref "R96") (pin "2") (pinfunction "2_2") (pintype "passive"))
      (node (ref "T3") (pin "2") (pinfunction "B_2") (pintype "passive"))
    )
    (net (code "175") (name "SLIDE") (class "Default")
      (node (ref "IC4") (pin "18") (pinfunction "[A8/PCINT8]_PC0_18") (pintype "input"))
      (node (ref "R22") (pin "1") (pinfunction "1_1") (pintype "passive"))
    )
    (net (code "176") (name "SPI_CLK") (class "Default")
      (node (ref "IC10") (pin "11") (pinfunction "SCK_11") (pintype "input"))
      (node (ref "IC11") (pin "2") (pinfunction "CLK_2") (pintype "input"))
      (node (ref "IC12") (pin "11") (pinfunction "SCK_11") (pintype "input"))
      (node (ref "IC13") (pin "11") (pinfunction "SCK_11") (pintype "input"))
      (node (ref "IC14") (pin "11") (pinfunction "SCK_11") (pintype "input"))
      (node (ref "IC4") (pin "3") (pinfunction "[SCK]_PB7_3") (pintype "bidirectional"))
      (node (ref "IC6") (pin "6") (pinfunction "SCK_6") (pintype "bidirectional"))
      (node (ref "IC7") (pin "2") (pinfunction "CLK_2") (pintype "input"))
      (node (ref "IC8") (pin "2") (pinfunction "CLK_2") (pintype "input"))
      (node (ref "IC9") (pin "11") (pinfunction "SCK_11") (pintype "input"))
    )
    (net (code "177") (name "SPI_IN") (class "Default")
      (node (ref "IC4") (pin "1") (pinfunction "[MOSI]_PB5_1") (pintype "bidirectional"))
      (node (ref "IC6") (pin "5") (pinfunction "SI_5") (pintype "bidirectional"))
    )
    (net (code "178") (name "SPI_OUT") (class "Default")
      (node (ref "IC4") (pin "2") (pinfunction "[MISO]_PB6_2") (pintype "bidirectional"))
      (node (ref "IC5") (pin "8") (pinfunction "3Y_8") (pintype "bidirectional"))
      (node (ref "IC6") (pin "2") (pinfunction "SO_2") (pintype "input"))
    )
    (net (code "179") (name "SWITCH_LATCH") (class "Default")
      (node (ref "IC11") (pin "1") (pinfunction "SH/~{LD}_1") (pintype "input"))
      (node (ref "IC5") (pin "10") (pinfunction "3OE_10") (pintype "bidirectional"))
      (node (ref "IC6") (pin "1") (pinfunction "CS/_1") (pintype "input"))
      (node (ref "IC7") (pin "1") (pinfunction "SH/~{LD}_1") (pintype "input"))
      (node (ref "IC8") (pin "1") (pinfunction "SH/~{LD}_1") (pintype "input"))
    )
    (net (code "180") (name "VCC") (class "Default")
      (node (ref "C10") (pin "2") (pinfunction "2_2") (pintype "bidirectional"))
      (node (ref "C11") (pin "2") (pinfunction "2_2") (pintype "bidirectional"))
      (node (ref "C12") (pin "+") (pinfunction "+_+") (pintype "passive"))
      (node (ref "C13") (pin "2") (pinfunction "2_2") (pintype "bidirectional"))
      (node (ref "C3") (pin "2") (pinfunction "2_2") (pintype "bidirectional"))
      (node (ref "C4") (pin "2") (pinfunction "2_2") (pintype "bidirectional"))
      (node (ref "C5") (pin "2") (pinfunction "2_2") (pintype "bidirectional"))
      (node (ref "C6") (pin "2") (pinfunction "2_2") (pintype "bidirectional"))
      (node (ref "C7") (pin "2") (pinfunction "2_2") (pintype "bidirectional"))
      (node (ref "C8") (pin "2") (pinfunction "2_2") (pintype "bidirectional"))
      (node (ref "C9") (pin "2") (pinfunction "2_2") (pintype "bidirectional"))
      (node (ref "D1") (pin "C") (pinfunction "C_C") (pintype "passive"))
      (node (ref "IC1") (pin "16") (pinfunction "VCC_16") (pintype "power_in"))
      (node (ref "IC10") (pin "10") (pinfunction "SCL_10") (pintype "input"))
      (node (ref "IC12") (pin "10") (pinfunction "SCL_10") (pintype "input"))
      (node (ref "IC13") (pin "10") (pinfunction "SCL_10") (pintype "input"))
      (node (ref "IC14") (pin "10") (pinfunction "SCL_10") (pintype "input"))
      (node (ref "IC2") (pin "8") (pinfunction "VCC_8") (pintype "power_in"))
      (node (ref "IC3") (pin "14") (pinfunction "VDD_14") (pintype "power_in"))
      (node (ref "IC4") (pin "6") (pinfunction "VCC_6") (pintype "power_in"))
      (node (ref "IC5") (pin "1") (pinfunction "1OE_1") (pintype "bidirectional"))
      (node (ref "IC5") (pin "14") (pinfunction "VCC_14") (pintype "bidirectional"))
      (node (ref "IC6") (pin "3") (pinfunction "WP/_3") (pintype "input"))
      (node (ref "IC6") (pin "7") (pinfunction "HOLD/_7") (pintype "input"))
      (node (ref "IC6") (pin "8") (pinfunction "VCC_8") (pintype "power_in"))
      (node (ref "IC9") (pin "10") (pinfunction "SCL_10") (pintype "input"))
      (node (ref "R19") (pin "2") (pinfunction "2_2") (pintype "passive"))
      (node (ref "R20") (pin "2") (pinfunction "2_2") (pintype "passive"))
      (node (ref "R24") (pin "2") (pinfunction "2_2") (pintype "passive"))
      (node (ref "R92") (pin "2") (pinfunction "2_2") (pintype "passive"))
      (node (ref "R97") (pin "2") (pinfunction "2_2") (pintype "passive"))
      (node (ref "S1") (pin "3") (pinfunction "3_3") (pintype "passive"))
      (node (ref "S10") (pin "3") (pinfunction "3_3") (pintype "passive"))
      (node (ref "S11") (pin "3") (pinfunction "3_3") (pintype "passive"))
      (node (ref "S12") (pin "3") (pinfunction "3_3") (pintype "passive"))
      (node (ref "S13") (pin "3") (pinfunction "3_3") (pintype "passive"))
      (node (ref "S14") (pin "3") (pinfunction "3_3") (pintype "passive"))
      (node (ref "S15") (pin "3") (pinfunction "3_3") (pintype "passive"))
      (node (ref "S16") (pin "3") (pinfunction "3_3") (pintype "passive"))
      (node (ref "S17") (pin "3") (pinfunction "3_3") (pintype "passive"))
      (node (ref "S18") (pin "3") (pinfunction "3_3") (pintype "passive"))
      (node (ref "S19") (pin "3") (pinfunction "3_3") (pintype "passive"))
      (node (ref "S2") (pin "3") (pinfunction "3_3") (pintype "passive"))
      (node (ref "S20") (pin "3") (pinfunction "3_3") (pintype "passive"))
      (node (ref "S21") (pin "3") (pinfunction "3_3") (pintype "passive"))
      (node (ref "S22") (pin "3") (pinfunction "3_3") (pintype "passive"))
      (node (ref "S23") (pin "3") (pinfunction "3_3") (pintype "passive"))
      (node (ref "S24") (pin "3") (pinfunction "3_3") (pintype "passive"))
      (node (ref "S3") (pin "3") (pinfunction "3_3") (pintype "passive"))
      (node (ref "S4") (pin "3") (pinfunction "3_3") (pintype "passive"))
      (node (ref "S5") (pin "3") (pinfunction "3_3") (pintype "passive"))
      (node (ref "S6") (pin "3") (pinfunction "3_3") (pintype "passive"))
      (node (ref "S7") (pin "3") (pinfunction "3_3") (pintype "passive"))
      (node (ref "S8") (pin "3") (pinfunction "3_3") (pintype "passive"))
      (node (ref "S9") (pin "3") (pinfunction "3_3") (pintype "passive"))
      (node (ref "T2") (pin "1") (pinfunction "E_1") (pintype "passive"))
    )
    (net (code "181") (name "VCC_1") (class "Default")
      (node (ref "IC4") (pin "17") (pinfunction "VCC_1_17") (pintype "power_in"))
    )
    (net (code "182") (name "VCC_2") (class "Default")
      (node (ref "IC4") (pin "38") (pinfunction "VCC_2_38") (pintype "power_in"))
    )
    (net (code "183") (name "unconnected-(IC1-~{CLR}-Pad1)") (class "Default")
      (node (ref "IC1") (pin "1") (pinfunction "~{CLR}_1") (pintype "bidirectional"))
    )
    (net (code "184") (name "unconnected-(IC2-2IN+-Pad5)") (class "Default")
      (node (ref "IC2") (pin "5") (pinfunction "2IN+_5") (pintype "input"))
    )
    (net (code "185") (name "unconnected-(IC2-2IN--Pad6)") (class "Default")
      (node (ref "IC2") (pin "6") (pinfunction "2IN-_6") (pintype "input"))
    )
    (net (code "186") (name "unconnected-(IC2-2OUT-Pad7)") (class "Default")
      (node (ref "IC2") (pin "7") (pinfunction "2OUT_7") (pintype "output"))
    )
    (net (code "187") (name "unconnected-(IC3-CONTROL_C-Pad6)") (class "Default")
      (node (ref "IC3") (pin "6") (pinfunction "CONTROL_C_6") (pintype "input"))
    )
    (net (code "188") (name "unconnected-(IC3-CONTROL_D-Pad12)") (class "Default")
      (node (ref "IC3") (pin "12") (pinfunction "CONTROL_D_12") (pintype "input"))
    )
    (net (code "189") (name "unconnected-(IC3-SIG_C_IN{slash}OUT-Pad8)") (class "Default")
      (node (ref "IC3") (pin "8") (pinfunction "SIG_C_IN/OUT_8") (pintype "input"))
    )
    (net (code "190") (name "unconnected-(IC3-SIG_C_OUT{slash}IN-Pad9)") (class "Default")
      (node (ref "IC3") (pin "9") (pinfunction "SIG_C_OUT/IN_9") (pintype "output"))
    )
    (net (code "191") (name "unconnected-(IC3-SIG_D_IN{slash}OUT-Pad11)") (class "Default")
      (node (ref "IC3") (pin "11") (pinfunction "SIG_D_IN/OUT_11") (pintype "input"))
    )
    (net (code "192") (name "unconnected-(IC3-SIG_D_OUT{slash}IN-Pad10)") (class "Default")
      (node (ref "IC3") (pin "10") (pinfunction "SIG_D_OUT/IN_10") (pintype "output"))
    )
    (net (code "193") (name "unconnected-(IC4-PA0_[AD0{slash}PCINT0]-Pad37)") (class "Default")
      (node (ref "IC4") (pin "37") (pinfunction "PA0_[AD0/PCINT0]_37") (pintype "input"))
    )
    (net (code "194") (name "unconnected-(IC4-PA1_[AD1{slash}PCINT1]-Pad36)") (class "Default")
      (node (ref "IC4") (pin "36") (pinfunction "PA1_[AD1/PCINT1]_36") (pintype "input"))
    )
    (net (code "195") (name "unconnected-(IC4-PA2_[AD2{slash}PCINT2]-Pad35)") (class "Default")
      (node (ref "IC4") (pin "35") (pinfunction "PA2_[AD2/PCINT2]_35") (pintype "input"))
    )
    (net (code "196") (name "unconnected-(IC4-PA3_[AD3{slash}PCINT3]-Pad34)") (class "Default")
      (node (ref "IC4") (pin "34") (pinfunction "PA3_[AD3/PCINT3]_34") (pintype "input"))
    )
    (net (code "197") (name "unconnected-(IC4-PA4_[AD4{slash}PCINT4]-Pad33)") (class "Default")
      (node (ref "IC4") (pin "33") (pinfunction "PA4_[AD4/PCINT4]_33") (pintype "input"))
    )
    (net (code "198") (name "unconnected-(IC4-PA5_[AD5{slash}PCINT5]-Pad32)") (class "Default")
      (node (ref "IC4") (pin "32") (pinfunction "PA5_[AD5/PCINT5]_32") (pintype "input"))
    )
    (net (code "199") (name "unconnected-(IC4-PA6_[AD6{slash}PCINT6]-Pad31)") (class "Default")
      (node (ref "IC4") (pin "31") (pinfunction "PA6_[AD6/PCINT6]_31") (pintype "input"))
    )
    (net (code "200") (name "unconnected-(IC4-PB0_[OC0{slash}T0]-Pad40)") (class "Default")
      (node (ref "IC4") (pin "40") (pinfunction "PB0_[OC0/T0]_40") (pintype "bidirectional"))
    )
    (net (code "201") (name "unconnected-(IC4-PB1_[OC2{slash}T1]-Pad41)") (class "Default")
      (node (ref "IC4") (pin "41") (pinfunction "PB1_[OC2/T1]_41") (pintype "bidirectional"))
    )
    (net (code "202") (name "unconnected-(IC4-PB2_[RXD1{slash}AIN0]-Pad42)") (class "Default")
      (node (ref "IC4") (pin "42") (pinfunction "PB2_[RXD1/AIN0]_42") (pintype "input"))
    )
    (net (code "203") (name "unconnected-(IC4-PB3_[TXD1{slash}AIN1]-Pad43)") (class "Default")
      (node (ref "IC4") (pin "43") (pinfunction "PB3_[TXD1/AIN1]_43") (pintype "input"))
    )
    (net (code "204") (name "unconnected-(IC4-PB4_[~{SS}{slash}OC3B]-Pad44)") (class "Default")
      (node (ref "IC4") (pin "44") (pinfunction "PB4_[~{SS}/OC3B]_44") (pintype "bidirectional"))
    )
    (net (code "205") (name "unconnected-(IC4-PE0_[ICP1{slash}INT2]-Pad29)") (class "Default")
      (node (ref "IC4") (pin "29") (pinfunction "PE0_[ICP1/INT2]_29") (pintype "input"))
    )
    (net (code "206") (name "unconnected-(IC4-[INT0{slash}XCK1]_PD2-Pad8)") (class "Default")
      (node (ref "IC4") (pin "8") (pinfunction "[INT0/XCK1]_PD2_8") (pintype "input"))
    )
    (net (code "207") (name "unconnected-(IC4-[INT1{slash}ICP3]_PD3-Pad9)") (class "Default")
      (node (ref "IC4") (pin "9") (pinfunction "[INT1/ICP3]_PD3_9") (pintype "input"))
    )
    (net (code "208") (name "unconnected-(IC4-[OC1A{slash}TOSC2]_PD5-Pad11)") (class "Default")
      (node (ref "IC4") (pin "11") (pinfunction "[OC1A/TOSC2]_PD5_11") (pintype "bidirectional"))
    )
    (net (code "209") (name "unconnected-(IC4-[RXD0]_PD0-Pad5)") (class "Default")
      (node (ref "IC4") (pin "5") (pinfunction "[RXD0]_PD0_5") (pintype "bidirectional"))
    )
    (net (code "210") (name "unconnected-(IC4-[TOSC1{slash}XCK0{slash}OC3A]_PD4-Pad10)") (class "Default")
      (node (ref "IC4") (pin "10") (pinfunction "[TOSC1/XCK0/OC3A]_PD4_10") (pintype "bidirectional"))
    )
    (net (code "211") (name "unconnected-(IC4-[TXD0]_PD1-Pad7)") (class "Default")
      (node (ref "IC4") (pin "7") (pinfunction "[TXD0]_PD1_7") (pintype "bidirectional"))
    )
    (net (code "212") (name "unconnected-(IC4-[~{RD]_PD7}-Pad13)") (class "Default")
      (node (ref "IC4") (pin "13") (pinfunction "[~{RD]_PD7}_13") (pintype "bidirectional"))
    )
    (net (code "213") (name "unconnected-(IC4-[~{WR]_PD6}-Pad12)") (class "Default")
      (node (ref "IC4") (pin "12") (pinfunction "[~{WR]_PD6}_12") (pintype "bidirectional"))
    )
    (net (code "214") (name "unconnected-(IC5-2A-Pad5)") (class "Default")
      (node (ref "IC5") (pin "5") (pinfunction "2A_5") (pintype "bidirectional"))
    )
    (net (code "215") (name "unconnected-(IC5-2OE-Pad4)") (class "Default")
      (node (ref "IC5") (pin "4") (pinfunction "2OE_4") (pintype "bidirectional"))
    )
    (net (code "216") (name "unconnected-(IC5-2Y-Pad6)") (class "Default")
      (node (ref "IC5") (pin "6") (pinfunction "2Y_6") (pintype "bidirectional"))
    )
    (net (code "217") (name "unconnected-(IC5-4A-Pad12)") (class "Default")
      (node (ref "IC5") (pin "12") (pinfunction "4A_12") (pintype "bidirectional"))
    )
    (net (code "218") (name "unconnected-(IC5-4OE-Pad13)") (class "Default")
      (node (ref "IC5") (pin "13") (pinfunction "4OE_13") (pintype "bidirectional"))
    )
    (net (code "219") (name "unconnected-(IC5-4Y-Pad11)") (class "Default")
      (node (ref "IC5") (pin "11") (pinfunction "4Y_11") (pintype "bidirectional"))
    )
    (net (code "220") (name "unconnected-(IC7A-~{QH}-Pad7)") (class "Default")
      (node (ref "IC7") (pin "7") (pinfunction "~{QH}_7") (pintype "output"))
    )
    (net (code "221") (name "unconnected-(IC8A-~{QH}-Pad7)") (class "Default")
      (node (ref "IC8") (pin "7") (pinfunction "~{QH}_7") (pintype "output"))
    )
    (net (code "222") (name "unconnected-(IC9A-QH*-Pad9)") (class "Default")
      (node (ref "IC9") (pin "9") (pinfunction "QH*_9") (pintype "tri_state"))
    )
    (net (code "223") (name "unconnected-(IC9A-SER-Pad14)") (class "Default")
      (node (ref "IC9") (pin "14") (pinfunction "SER_14") (pintype "input"))
    )
    (net (code "224") (name "unconnected-(IC10A-QH*-Pad9)") (class "Default")
      (node (ref "IC10") (pin "9") (pinfunction "QH*_9") (pintype "tri_state"))
    )
    (net (code "225") (name "unconnected-(IC10A-SER-Pad14)") (class "Default")
      (node (ref "IC10") (pin "14") (pinfunction "SER_14") (pintype "input"))
    )
    (net (code "226") (name "unconnected-(IC11A-~{QH}-Pad7)") (class "Default")
      (node (ref "IC11") (pin "7") (pinfunction "~{QH}_7") (pintype "output"))
    )
    (net (code "227") (name "unconnected-(IC12A-QH*-Pad9)") (class "Default")
      (node (ref "IC12") (pin "9") (pinfunction "QH*_9") (pintype "tri_state"))
    )
    (net (code "228") (name "unconnected-(IC12A-SER-Pad14)") (class "Default")
      (node (ref "IC12") (pin "14") (pinfunction "SER_14") (pintype "input"))
    )
    (net (code "229") (name "unconnected-(IC13A-QH*-Pad9)") (class "Default")
      (node (ref "IC13") (pin "9") (pinfunction "QH*_9") (pintype "tri_state"))
    )
    (net (code "230") (name "unconnected-(IC13A-SER-Pad14)") (class "Default")
      (node (ref "IC13") (pin "14") (pinfunction "SER_14") (pintype "input"))
    )
    (net (code "231") (name "unconnected-(IC14A-QH*-Pad9)") (class "Default")
      (node (ref "IC14") (pin "9") (pinfunction "QH*_9") (pintype "tri_state"))
    )
    (net (code "232") (name "unconnected-(IC14A-SER-Pad14)") (class "Default")
      (node (ref "IC14") (pin "14") (pinfunction "SER_14") (pintype "input"))
    )
    (net (code "233") (name "unconnected-(S1-Pad4)") (class "Default")
      (node (ref "S1") (pin "4") (pinfunction "4_4") (pintype "passive"))
    )
    (net (code "234") (name "unconnected-(S2-Pad4)") (class "Default")
      (node (ref "S2") (pin "4") (pinfunction "4_4") (pintype "passive"))
    )
    (net (code "235") (name "unconnected-(S3-Pad4)") (class "Default")
      (node (ref "S3") (pin "4") (pinfunction "4_4") (pintype "passive"))
    )
    (net (code "236") (name "unconnected-(S4-Pad4)") (class "Default")
      (node (ref "S4") (pin "4") (pinfunction "4_4") (pintype "passive"))
    )
    (net (code "237") (name "unconnected-(S5-Pad4)") (class "Default")
      (node (ref "S5") (pin "4") (pinfunction "4_4") (pintype "passive"))
    )
    (net (code "238") (name "unconnected-(S6-Pad4)") (class "Default")
      (node (ref "S6") (pin "4") (pinfunction "4_4") (pintype "passive"))
    )
    (net (code "239") (name "unconnected-(S7-Pad4)") (class "Default")
      (node (ref "S7") (pin "4") (pinfunction "4_4") (pintype "passive"))
    )
    (net (code "240") (name "unconnected-(S8-Pad4)") (class "Default")
      (node (ref "S8") (pin "4") (pinfunction "4_4") (pintype "passive"))
    )
    (net (code "241") (name "unconnected-(S9-Pad4)") (class "Default")
      (node (ref "S9") (pin "4") (pinfunction "4_4") (pintype "passive"))
    )
    (net (code "242") (name "unconnected-(S10-Pad4)") (class "Default")
      (node (ref "S10") (pin "4") (pinfunction "4_4") (pintype "passive"))
    )
    (net (code "243") (name "unconnected-(S11-Pad4)") (class "Default")
      (node (ref "S11") (pin "4") (pinfunction "4_4") (pintype "passive"))
    )
    (net (code "244") (name "unconnected-(S12-Pad4)") (class "Default")
      (node (ref "S12") (pin "4") (pinfunction "4_4") (pintype "passive"))
    )
    (net (code "245") (name "unconnected-(S13-Pad4)") (class "Default")
      (node (ref "S13") (pin "4") (pinfunction "4_4") (pintype "passive"))
    )
    (net (code "246") (name "unconnected-(S14-Pad4)") (class "Default")
      (node (ref "S14") (pin "4") (pinfunction "4_4") (pintype "passive"))
    )
    (net (code "247") (name "unconnected-(S15-Pad4)") (class "Default")
      (node (ref "S15") (pin "4") (pinfunction "4_4") (pintype "passive"))
    )
    (net (code "248") (name "unconnected-(S16-Pad4)") (class "Default")
      (node (ref "S16") (pin "4") (pinfunction "4_4") (pintype "passive"))
    )
    (net (code "249") (name "unconnected-(S17-Pad4)") (class "Default")
      (node (ref "S17") (pin "4") (pinfunction "4_4") (pintype "passive"))
    )
    (net (code "250") (name "unconnected-(S18-Pad4)") (class "Default")
      (node (ref "S18") (pin "4") (pinfunction "4_4") (pintype "passive"))
    )
    (net (code "251") (name "unconnected-(S19-Pad4)") (class "Default")
      (node (ref "S19") (pin "4") (pinfunction "4_4") (pintype "passive"))
    )
    (net (code "252") (name "unconnected-(S20-Pad4)") (class "Default")
      (node (ref "S20") (pin "4") (pinfunction "4_4") (pintype "passive"))
    )
    (net (code "253") (name "unconnected-(S21-Pad4)") (class "Default")
      (node (ref "S21") (pin "4") (pinfunction "4_4") (pintype "passive"))
    )
    (net (code "254") (name "unconnected-(S22-Pad4)") (class "Default")
      (node (ref "S22") (pin "4") (pinfunction "4_4") (pintype "passive"))
    )
    (net (code "255") (name "unconnected-(S23-Pad4)") (class "Default")
      (node (ref "S23") (pin "4") (pinfunction "4_4") (pintype "passive"))
    )
    (net (code "256") (name "unconnected-(S24-Pad4)") (class "Default")
      (node (ref "S24") (pin "4") (pinfunction "4_4") (pintype "passive"))
    )
  )
)
